# GPSDOCXO_STMv2.net
KiCad netlist of a schematic drawn in EAGLE
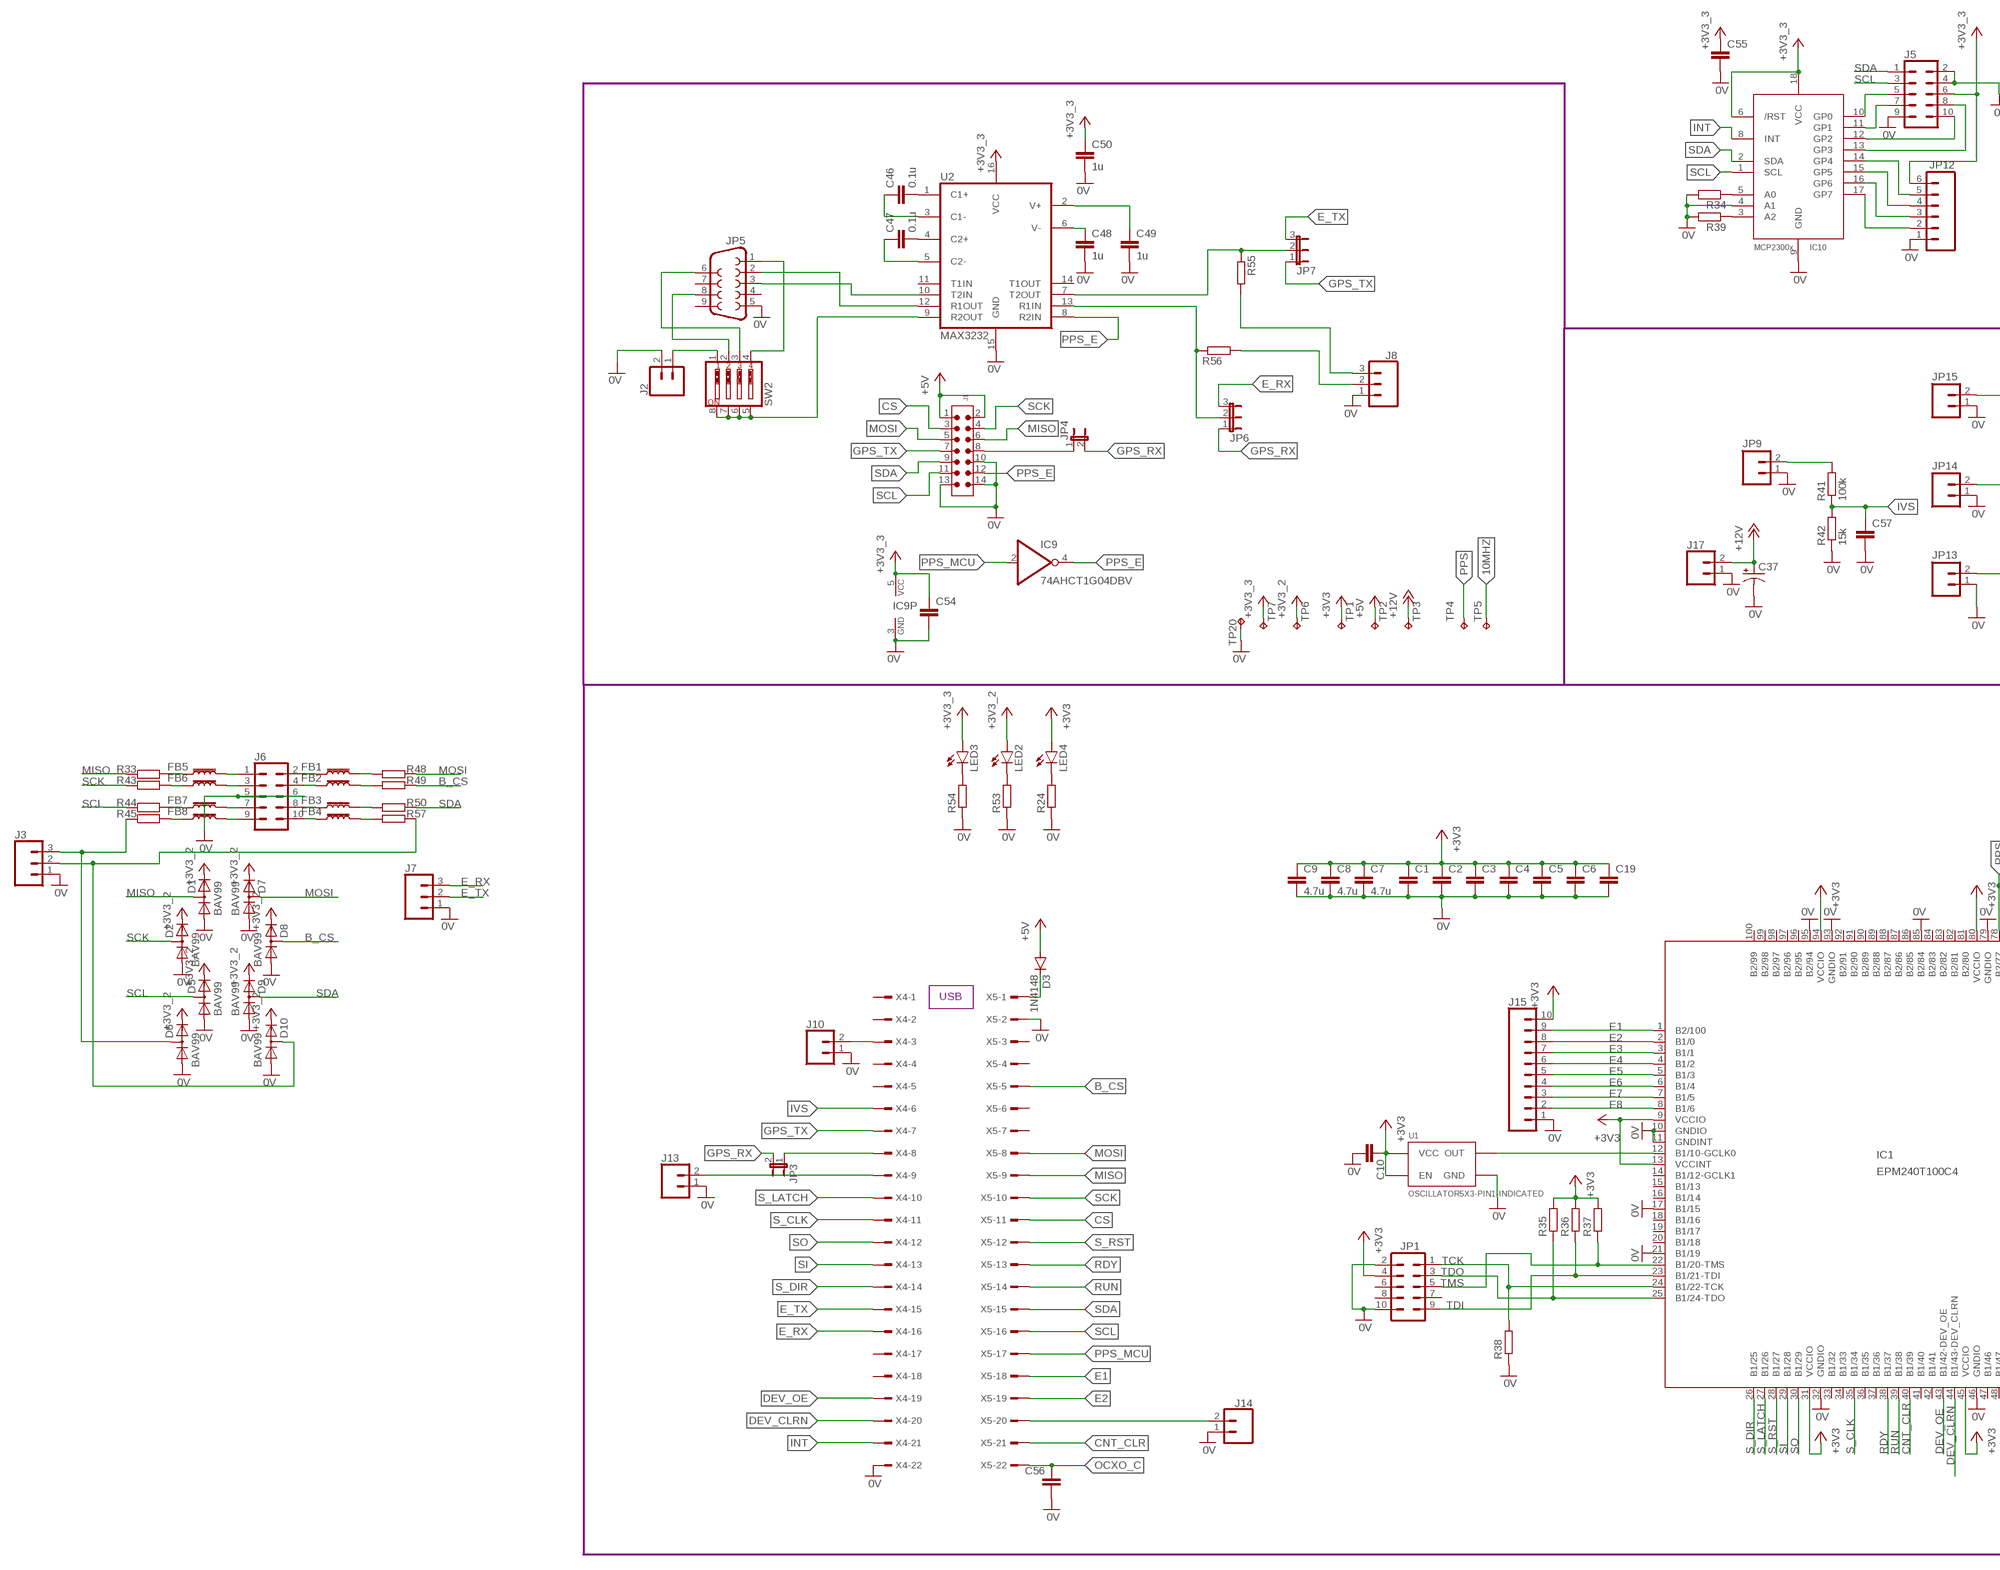
[diagram p0: schematic, sheet 1, part 1 of 2]
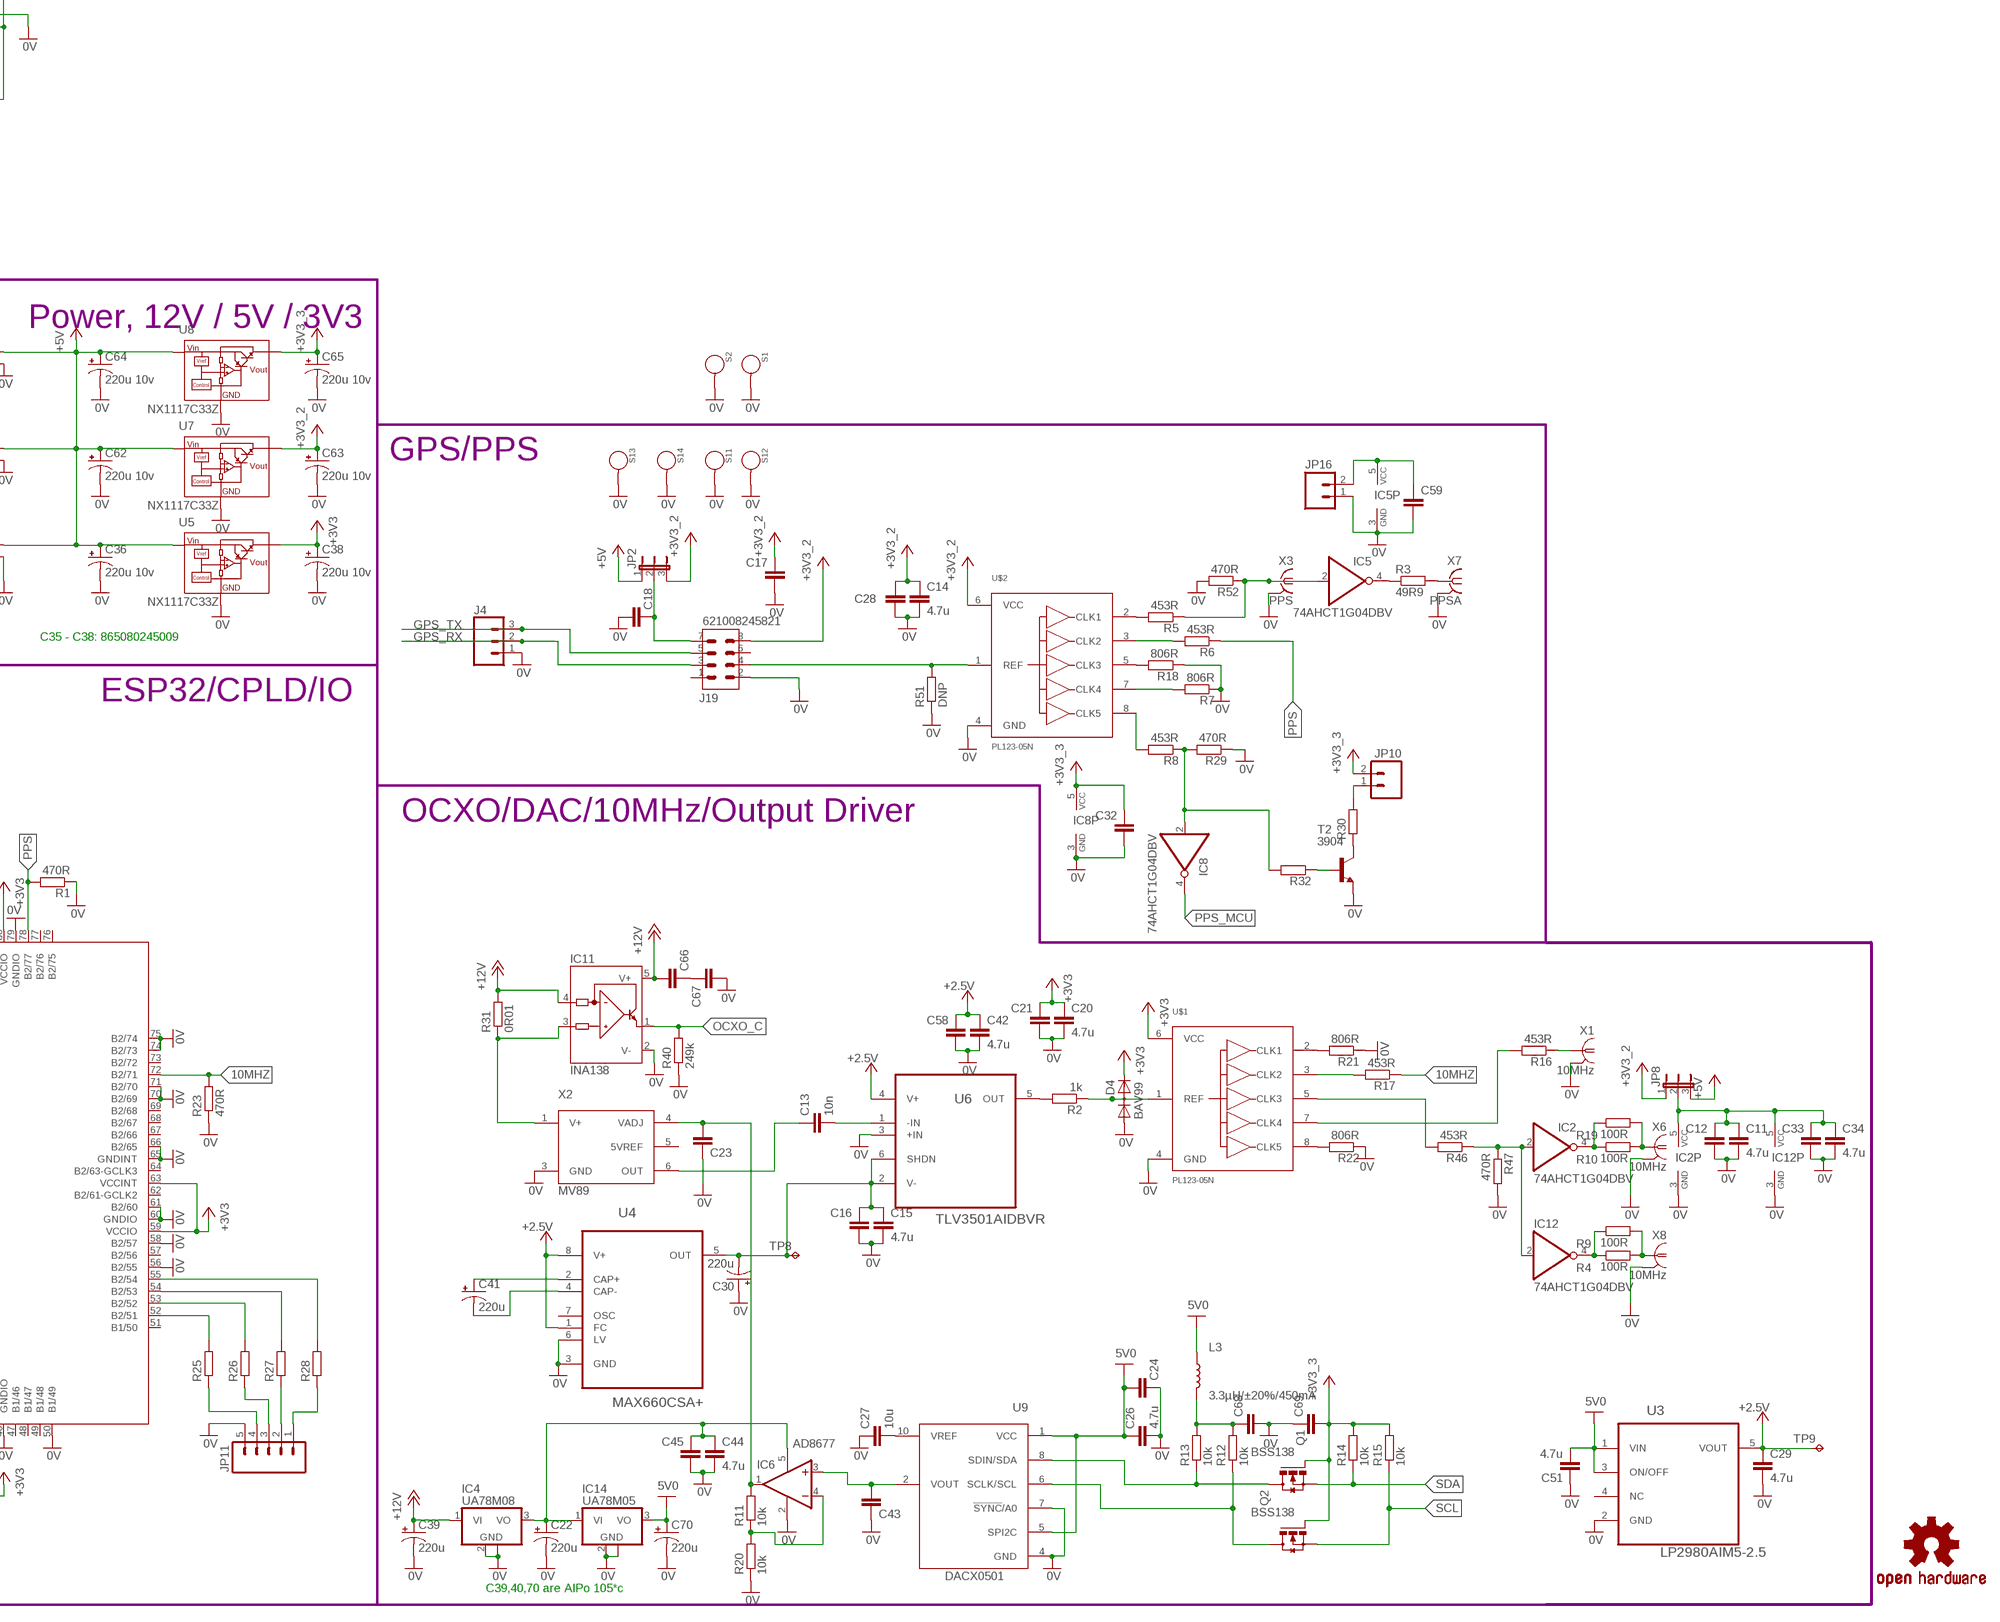
[diagram p1: schematic, sheet 1, part 2 of 2]

(export (version "E")
  (design (tool "Eeschema 10.0.6"))
  (components
    (comp (ref "C1")
      (value "C-EUC0603")
      (footprint "eagle-import:C0603")
      (libsource (lib "eagle-import") (part "C-EUC0603"))
    )
    (comp (ref "C2")
      (value "C-EUC0603")
      (footprint "eagle-import:C0603")
      (libsource (lib "eagle-import") (part "C-EUC0603"))
    )
    (comp (ref "C3")
      (value "C-EUC0603")
      (footprint "eagle-import:C0603")
      (libsource (lib "eagle-import") (part "C-EUC0603"))
    )
    (comp (ref "C4")
      (value "C-EUC0603")
      (footprint "eagle-import:C0603")
      (libsource (lib "eagle-import") (part "C-EUC0603"))
    )
    (comp (ref "C5")
      (value "C-EUC0603")
      (footprint "eagle-import:C0603")
      (libsource (lib "eagle-import") (part "C-EUC0603"))
    )
    (comp (ref "C6")
      (value "C-EUC0603")
      (footprint "eagle-import:C0603")
      (libsource (lib "eagle-import") (part "C-EUC0603"))
    )
    (comp (ref "C7")
      (value "4.7u")
      (footprint "eagle-import:C0805")
      (libsource (lib "eagle-import") (part "C-EUC0805"))
    )
    (comp (ref "C8")
      (value "4.7u")
      (footprint "eagle-import:C0805")
      (libsource (lib "eagle-import") (part "C-EUC0805"))
    )
    (comp (ref "C9")
      (value "4.7u")
      (footprint "eagle-import:C0805")
      (libsource (lib "eagle-import") (part "C-EUC0805"))
    )
    (comp (ref "C10")
      (value "C-EUC0603")
      (footprint "eagle-import:C0603")
      (libsource (lib "eagle-import") (part "C-EUC0603"))
    )
    (comp (ref "C11")
      (value "4.7u")
      (footprint "eagle-import:C0805")
      (libsource (lib "eagle-import") (part "C-EUC0805"))
    )
    (comp (ref "C12")
      (value "C-EUC0603")
      (footprint "eagle-import:C0603")
      (libsource (lib "eagle-import") (part "C-EUC0603"))
    )
    (comp (ref "C13")
      (value "10n")
      (footprint "eagle-import:C0805")
      (libsource (lib "eagle-import") (part "C-EUC0805"))
    )
    (comp (ref "C14")
      (value "4.7u")
      (footprint "eagle-import:C0805")
      (libsource (lib "eagle-import") (part "C-EUC0805"))
    )
    (comp (ref "C15")
      (value "4.7u")
      (footprint "eagle-import:C0805")
      (libsource (lib "eagle-import") (part "C-EUC0805"))
    )
    (comp (ref "C16")
      (value "C-EUC0603")
      (footprint "eagle-import:C0603")
      (libsource (lib "eagle-import") (part "C-EUC0603"))
    )
    (comp (ref "C17")
      (value "C-EUC0805")
      (footprint "eagle-import:C0805")
      (libsource (lib "eagle-import") (part "C-EUC0805"))
    )
    (comp (ref "C18")
      (value "C-EUC0805")
      (footprint "eagle-import:C0805")
      (libsource (lib "eagle-import") (part "C-EUC0805"))
    )
    (comp (ref "C19")
      (value "C-EUC0603")
      (footprint "eagle-import:C0603")
      (libsource (lib "eagle-import") (part "C-EUC0603"))
    )
    (comp (ref "C20")
      (value "4.7u")
      (footprint "eagle-import:C0805")
      (libsource (lib "eagle-import") (part "C-EUC0805"))
    )
    (comp (ref "C21")
      (value "C-EUC0603")
      (footprint "eagle-import:C0603")
      (libsource (lib "eagle-import") (part "C-EUC0603"))
    )
    (comp (ref "C22")
      (value "220u")
      (footprint "eagle-import:153CLV-0605")
      (libsource (lib "eagle-import") (part "CPOL-US153CLV-0605"))
    )
    (comp (ref "C23")
      (value "C-EUC0603")
      (footprint "eagle-import:C0603")
      (libsource (lib "eagle-import") (part "C-EUC0603"))
    )
    (comp (ref "C24")
      (value "C-EUC0603")
      (footprint "eagle-import:C0603")
      (libsource (lib "eagle-import") (part "C-EUC0603"))
    )
    (comp (ref "C26")
      (value "4.7u")
      (footprint "eagle-import:C0805")
      (libsource (lib "eagle-import") (part "C-EUC0805"))
    )
    (comp (ref "C27")
      (value "10u")
      (footprint "eagle-import:C0805")
      (libsource (lib "eagle-import") (part "C-EUC0805"))
    )
    (comp (ref "C28")
      (value "C-EUC0603")
      (footprint "eagle-import:C0603")
      (libsource (lib "eagle-import") (part "C-EUC0603"))
    )
    (comp (ref "C29")
      (value "4.7u")
      (footprint "eagle-import:C0805")
      (libsource (lib "eagle-import") (part "C-EUC0805"))
    )
    (comp (ref "C30")
      (value "220u")
      (footprint "eagle-import:153CLV-1010")
      (libsource (lib "eagle-import") (part "CPOL-US153CLV-1010"))
    )
    (comp (ref "C32")
      (value "C-EUC0603")
      (footprint "eagle-import:C0603")
      (libsource (lib "eagle-import") (part "C-EUC0603"))
    )
    (comp (ref "C33")
      (value "C-EUC0603")
      (footprint "eagle-import:C0603")
      (libsource (lib "eagle-import") (part "C-EUC0603"))
    )
    (comp (ref "C34")
      (value "4.7u")
      (footprint "eagle-import:C0805")
      (libsource (lib "eagle-import") (part "C-EUC0805"))
    )
    (comp (ref "C36")
      (value "220u 10v")
      (footprint "eagle-import:153CLV-0605")
      (libsource (lib "eagle-import") (part "CPOL-US153CLV-0605"))
    )
    (comp (ref "C37")
      (value "CPOL-USE3.5-8")
      (footprint "eagle-import:E3,5-8")
      (libsource (lib "eagle-import") (part "CPOL-USE3.5-8"))
    )
    (comp (ref "C38")
      (value "220u 10v")
      (footprint "eagle-import:153CLV-0605")
      (libsource (lib "eagle-import") (part "CPOL-US153CLV-0605"))
    )
    (comp (ref "C39")
      (value "220u")
      (footprint "eagle-import:153CLV-1010")
      (libsource (lib "eagle-import") (part "CPOL-US153CLV-1010"))
    )
    (comp (ref "C41")
      (value "220u")
      (footprint "eagle-import:153CLV-1010")
      (libsource (lib "eagle-import") (part "CPOL-US153CLV-1010"))
    )
    (comp (ref "C42")
      (value "4.7u")
      (footprint "eagle-import:C0805")
      (libsource (lib "eagle-import") (part "C-EUC0805"))
    )
    (comp (ref "C43")
      (value "C-EUC0603")
      (footprint "eagle-import:C0603")
      (libsource (lib "eagle-import") (part "C-EUC0603"))
    )
    (comp (ref "C44")
      (value "4.7u")
      (footprint "eagle-import:C0805")
      (libsource (lib "eagle-import") (part "C-EUC0805"))
    )
    (comp (ref "C45")
      (value "C-EUC0603")
      (footprint "eagle-import:C0603")
      (libsource (lib "eagle-import") (part "C-EUC0603"))
    )
    (comp (ref "C46")
      (value "0.1u")
      (footprint "eagle-import:C0603")
      (libsource (lib "eagle-import") (part "C-EUC0603"))
    )
    (comp (ref "C47")
      (value "0.1u")
      (footprint "eagle-import:C0603")
      (libsource (lib "eagle-import") (part "C-EUC0603"))
    )
    (comp (ref "C48")
      (value "1u")
      (footprint "eagle-import:C0603")
      (libsource (lib "eagle-import") (part "C-EUC0603"))
    )
    (comp (ref "C49")
      (value "1u")
      (footprint "eagle-import:C0603")
      (libsource (lib "eagle-import") (part "C-EUC0603"))
    )
    (comp (ref "C50")
      (value "1u")
      (footprint "eagle-import:C0603")
      (libsource (lib "eagle-import") (part "C-EUC0603"))
    )
    (comp (ref "C51")
      (value "4.7u")
      (footprint "eagle-import:C0805")
      (libsource (lib "eagle-import") (part "C-EUC0805"))
    )
    (comp (ref "C54")
      (value "C-EUC0603")
      (footprint "eagle-import:C0603")
      (libsource (lib "eagle-import") (part "C-EUC0603"))
    )
    (comp (ref "C55")
      (value "C-EUC0603")
      (footprint "eagle-import:C0603")
      (libsource (lib "eagle-import") (part "C-EUC0603"))
    )
    (comp (ref "C56")
      (value "C-EUC0603")
      (footprint "eagle-import:C0603")
      (libsource (lib "eagle-import") (part "C-EUC0603"))
    )
    (comp (ref "C57")
      (value "C-EUC0603")
      (footprint "eagle-import:C0603")
      (libsource (lib "eagle-import") (part "C-EUC0603"))
    )
    (comp (ref "C58")
      (value "C-EUC0603")
      (footprint "eagle-import:C0603")
      (libsource (lib "eagle-import") (part "C-EUC0603"))
    )
    (comp (ref "C59")
      (value "C-EUC0603")
      (footprint "eagle-import:C0603")
      (libsource (lib "eagle-import") (part "C-EUC0603"))
    )
    (comp (ref "C62")
      (value "220u 10v")
      (footprint "eagle-import:153CLV-0605")
      (libsource (lib "eagle-import") (part "CPOL-US153CLV-0605"))
    )
    (comp (ref "C63")
      (value "220u 10v")
      (footprint "eagle-import:153CLV-0605")
      (libsource (lib "eagle-import") (part "CPOL-US153CLV-0605"))
    )
    (comp (ref "C64")
      (value "220u 10v")
      (footprint "eagle-import:153CLV-0605")
      (libsource (lib "eagle-import") (part "CPOL-US153CLV-0605"))
    )
    (comp (ref "C65")
      (value "220u 10v")
      (footprint "eagle-import:153CLV-0605")
      (libsource (lib "eagle-import") (part "CPOL-US153CLV-0605"))
    )
    (comp (ref "C66")
      (value "C-EUC0603")
      (footprint "eagle-import:C0603")
      (libsource (lib "eagle-import") (part "C-EUC0603"))
    )
    (comp (ref "C67")
      (value "C-EUC0603")
      (footprint "eagle-import:C0603")
      (libsource (lib "eagle-import") (part "C-EUC0603"))
    )
    (comp (ref "C68")
      (value "C-EUC0603")
      (footprint "eagle-import:C0603")
      (libsource (lib "eagle-import") (part "C-EUC0603"))
    )
    (comp (ref "C69")
      (value "C-EUC0603")
      (footprint "eagle-import:C0603")
      (libsource (lib "eagle-import") (part "C-EUC0603"))
    )
    (comp (ref "C70")
      (value "220u")
      (footprint "eagle-import:153CLV-0605")
      (libsource (lib "eagle-import") (part "CPOL-US153CLV-0605"))
    )
    (comp (ref "D1")
      (value "BAV99")
      (footprint "eagle-import:SOT23")
      (libsource (lib "eagle-import") (part "BAV99"))
    )
    (comp (ref "D2")
      (value "BAV99")
      (footprint "eagle-import:SOT23")
      (libsource (lib "eagle-import") (part "BAV99"))
    )
    (comp (ref "D3")
      (value "1N4148")
      (footprint "eagle-import:DO35-7")
      (libsource (lib "eagle-import") (part "1N4148DO35-7"))
    )
    (comp (ref "D4")
      (value "BAV99")
      (footprint "eagle-import:SOT23")
      (libsource (lib "eagle-import") (part "BAV99"))
    )
    (comp (ref "D5")
      (value "BAV99")
      (footprint "eagle-import:SOT23")
      (libsource (lib "eagle-import") (part "BAV99"))
    )
    (comp (ref "D6")
      (value "BAV99")
      (footprint "eagle-import:SOT23")
      (libsource (lib "eagle-import") (part "BAV99"))
    )
    (comp (ref "D7")
      (value "BAV99")
      (footprint "eagle-import:SOT23")
      (libsource (lib "eagle-import") (part "BAV99"))
    )
    (comp (ref "D8")
      (value "BAV99")
      (footprint "eagle-import:SOT23")
      (libsource (lib "eagle-import") (part "BAV99"))
    )
    (comp (ref "D9")
      (value "BAV99")
      (footprint "eagle-import:SOT23")
      (libsource (lib "eagle-import") (part "BAV99"))
    )
    (comp (ref "D10")
      (value "BAV99")
      (footprint "eagle-import:SOT23")
      (libsource (lib "eagle-import") (part "BAV99"))
    )
    (comp (ref "FB1")
      (value "FERRITE_BEAD-0603")
      (footprint "eagle-import:0603")
      (libsource (lib "eagle-import") (part "FERRITE_BEAD-0603"))
    )
    (comp (ref "FB2")
      (value "FERRITE_BEAD-0603")
      (footprint "eagle-import:0603")
      (libsource (lib "eagle-import") (part "FERRITE_BEAD-0603"))
    )
    (comp (ref "FB3")
      (value "FERRITE_BEAD-0603")
      (footprint "eagle-import:0603")
      (libsource (lib "eagle-import") (part "FERRITE_BEAD-0603"))
    )
    (comp (ref "FB4")
      (value "FERRITE_BEAD-0603")
      (footprint "eagle-import:0603")
      (libsource (lib "eagle-import") (part "FERRITE_BEAD-0603"))
    )
    (comp (ref "FB5")
      (value "FERRITE_BEAD-0603")
      (footprint "eagle-import:0603")
      (libsource (lib "eagle-import") (part "FERRITE_BEAD-0603"))
    )
    (comp (ref "FB6")
      (value "FERRITE_BEAD-0603")
      (footprint "eagle-import:0603")
      (libsource (lib "eagle-import") (part "FERRITE_BEAD-0603"))
    )
    (comp (ref "FB7")
      (value "FERRITE_BEAD-0603")
      (footprint "eagle-import:0603")
      (libsource (lib "eagle-import") (part "FERRITE_BEAD-0603"))
    )
    (comp (ref "FB8")
      (value "FERRITE_BEAD-0603")
      (footprint "eagle-import:0603")
      (libsource (lib "eagle-import") (part "FERRITE_BEAD-0603"))
    )
    (comp (ref "IC1")
      (value "EPM240T100C4")
      (footprint "eagle-import:TQFP100")
      (libsource (lib "eagle-import") (part "EPM240T100C4"))
    )
    (comp (ref "IC2")
      (value "74AHCT1G04DBV")
      (footprint "eagle-import:SOT23-5")
      (libsource (lib "eagle-import") (part "741G04DBVAHCT"))
    )
    (comp (ref "IC4")
      (value "UA78M08")
      (footprint "eagle-import:SOT223")
      (libsource (lib "eagle-import") (part "UA78MDCY05"))
    )
    (comp (ref "IC5")
      (value "74AHCT1G04DBV")
      (footprint "eagle-import:SOT23-5")
      (libsource (lib "eagle-import") (part "741G04DBVAHCT"))
    )
    (comp (ref "IC6")
      (value "AD8677")
      (footprint "eagle-import:SOT23-5")
      (libsource (lib "eagle-import") (part "MCP601OT"))
    )
    (comp (ref "IC8")
      (value "74AHCT1G04DBV")
      (footprint "eagle-import:SOT23-5")
      (libsource (lib "eagle-import") (part "741G04DBVAHCT"))
    )
    (comp (ref "IC9")
      (value "74AHCT1G04DBV")
      (footprint "eagle-import:SOT23-5")
      (libsource (lib "eagle-import") (part "741G04DBVAHCT"))
    )
    (comp (ref "IC10")
      (value "MCP23008/SO")
      (footprint "eagle-import:SO18W")
      (libsource (lib "eagle-import") (part "MCP23008/SO"))
    )
    (comp (ref "IC11")
      (value "INA138")
      (footprint "eagle-import:SOT23-5")
      (fields (field (name "MF") "TEXAS INSTRUMENTS") (field (name "MPN") "INA138NA/250"))
      (libsource (lib "eagle-import") (part "INA138"))
    )
    (comp (ref "IC12")
      (value "74AHCT1G04DBV")
      (footprint "eagle-import:SOT23-5")
      (libsource (lib "eagle-import") (part "741G04DBVAHCT"))
    )
    (comp (ref "IC14")
      (value "UA78M05")
      (footprint "eagle-import:SOT223")
      (libsource (lib "eagle-import") (part "UA78MDCY05"))
    )
    (comp (ref "J1")
      (value "6120XX21621_61201421621")
      (footprint "eagle-import:61201421621")
      (libsource (lib "eagle-import") (part "6120XX21621_61201421621"))
    )
    (comp (ref "J2")
      (value "CONN_02")
      (footprint "eagle-import:1X02")
      (libsource (lib "eagle-import") (part "CONN_02"))
    )
    (comp (ref "J3")
      (value "M03POLAR")
      (footprint "eagle-import:MOLEX-1X3")
      (libsource (lib "eagle-import") (part "M03POLAR"))
    )
    (comp (ref "J4")
      (value "CONN_03")
      (footprint "eagle-import:1X03")
      (libsource (lib "eagle-import") (part "CONN_03"))
    )
    (comp (ref "J5")
      (value "CONN_05X2SHD-NS")
      (footprint "eagle-import:2X5-SHROUDED-NS")
      (libsource (lib "eagle-import") (part "CONN_05X2SHD-NS"))
    )
    (comp (ref "J6")
      (value "CONN_05X2RAF")
      (footprint "eagle-import:2X5-RAF")
      (libsource (lib "eagle-import") (part "CONN_05X2RAF"))
    )
    (comp (ref "J7")
      (value "M03POLAR")
      (footprint "eagle-import:MOLEX-1X3")
      (libsource (lib "eagle-import") (part "M03POLAR"))
    )
    (comp (ref "J8")
      (value "M03POLAR")
      (footprint "eagle-import:MOLEX-1X3")
      (libsource (lib "eagle-import") (part "M03POLAR"))
    )
    (comp (ref "J10")
      (value "CONN_02")
      (footprint "eagle-import:1X02")
      (libsource (lib "eagle-import") (part "CONN_02"))
    )
    (comp (ref "J13")
      (value "CONN_02")
      (footprint "eagle-import:1X02")
      (libsource (lib "eagle-import") (part "CONN_02"))
    )
    (comp (ref "J14")
      (value "CONN_02")
      (footprint "eagle-import:1X02")
      (libsource (lib "eagle-import") (part "CONN_02"))
    )
    (comp (ref "J15")
      (value "CONN_10NO_SILK_PTH_FEMALE")
      (footprint "eagle-import:1X10_NO_SILK")
      (libsource (lib "eagle-import") (part "CONN_10NO_SILK_PTH_FEMALE"))
    )
    (comp (ref "J17")
      (value "CONN_025MM")
      (footprint "eagle-import:SCREWTERMINAL-5MM-2")
      (libsource (lib "eagle-import") (part "CONN_025MM"))
    )
    (comp (ref "J19")
      (value "621008245821")
      (footprint "eagle-import:621008245821")
      (fields
        (field (name "MANUFACTURER") "Wurth Elektronik")
        (field (name "MPN") "621008245821 ")
        (field (name "CREATED_BY") "PCBLayout.com")
      )
      (libsource (lib "eagle-import") (part "621008245821"))
    )
    (comp (ref "JP1")
      (value "M05X2SHD-NS")
      (footprint "eagle-import:2X5-SHROUDED-NS")
      (libsource (lib "eagle-import") (part "M05X2SHD-NS"))
    )
    (comp (ref "JP2")
      (value "JP2E")
      (footprint "eagle-import:JP2")
      (libsource (lib "eagle-import") (part "JP2E"))
    )
    (comp (ref "JP3")
      (value "JP1E")
      (footprint "eagle-import:JP1")
      (libsource (lib "eagle-import") (part "JP1E"))
    )
    (comp (ref "JP4")
      (value "JP1E")
      (footprint "eagle-import:JP1")
      (libsource (lib "eagle-import") (part "JP1E"))
    )
    (comp (ref "JP5")
      (value "DB9FEMALE")
      (footprint "eagle-import:DB9")
      (libsource (lib "eagle-import") (part "DB9FEMALE"))
    )
    (comp (ref "JP6")
      (value "JP2E")
      (footprint "eagle-import:JP2")
      (libsource (lib "eagle-import") (part "JP2E"))
    )
    (comp (ref "JP7")
      (value "JP2E")
      (footprint "eagle-import:JP2")
      (libsource (lib "eagle-import") (part "JP2E"))
    )
    (comp (ref "JP8")
      (value "JP2E")
      (footprint "eagle-import:JP2")
      (libsource (lib "eagle-import") (part "JP2E"))
    )
    (comp (ref "JP9")
      (value "M02POLAR")
      (footprint "eagle-import:MOLEX-1X2")
      (libsource (lib "eagle-import") (part "M02POLAR"))
    )
    (comp (ref "JP10")
      (value "M02POLAR")
      (footprint "eagle-import:MOLEX-1X2")
      (libsource (lib "eagle-import") (part "M02POLAR"))
    )
    (comp (ref "JP11")
      (value "M05NO_SILK")
      (footprint "eagle-import:1X05_NO_SILK")
      (libsource (lib "eagle-import") (part "M05NO_SILK"))
    )
    (comp (ref "JP12")
      (value "M06SILK_FEMALE_PTH")
      (footprint "eagle-import:1X06")
      (libsource (lib "eagle-import") (part "M06SILK_FEMALE_PTH"))
    )
    (comp (ref "JP13")
      (value "M02POLAR")
      (footprint "eagle-import:MOLEX-1X2")
      (libsource (lib "eagle-import") (part "M02POLAR"))
    )
    (comp (ref "JP14")
      (value "M02POLAR")
      (footprint "eagle-import:MOLEX-1X2")
      (libsource (lib "eagle-import") (part "M02POLAR"))
    )
    (comp (ref "JP15")
      (value "M02POLAR")
      (footprint "eagle-import:MOLEX-1X2")
      (libsource (lib "eagle-import") (part "M02POLAR"))
    )
    (comp (ref "JP16")
      (value "M02POLAR")
      (footprint "eagle-import:MOLEX-1X2")
      (libsource (lib "eagle-import") (part "M02POLAR"))
    )
    (comp (ref "L3")
      (value "3.3µH/±20%/450mA")
      (footprint "eagle-import:0805")
      (libsource (lib "eagle-import") (part "INDUCTOR-0805-3.3UH"))
    )
    (comp (ref "LED2")
      (value "LED5MM")
      (footprint "eagle-import:LED5MM")
      (libsource (lib "eagle-import") (part "LED5MM"))
    )
    (comp (ref "LED3")
      (value "LED5MM")
      (footprint "eagle-import:LED5MM")
      (libsource (lib "eagle-import") (part "LED5MM"))
    )
    (comp (ref "LED4")
      (value "LED5MM")
      (footprint "eagle-import:LED5MM")
      (libsource (lib "eagle-import") (part "LED5MM"))
    )
    (comp (ref "LOGO1")
      (value "OSHW-LOGOL")
      (footprint "eagle-import:OSHW-LOGO-L")
      (libsource (lib "eagle-import") (part "OSHW-LOGOL"))
    )
    (comp (ref "Q1")
      (value "BSS138")
      (footprint "eagle-import:SOT23-3")
      (fields
        (field (name "DIGIKEY_PART_NUMBER") "BSS138CT-ND")
        (field (name "MANUFACTURER") "ON Semiconductor")
        (field (name "CREATED_BY") "PCBLayout.com")
      )
      (libsource (lib "eagle-import") (part "BSS138"))
    )
    (comp (ref "Q2")
      (value "BSS138")
      (footprint "eagle-import:SOT23-3")
      (fields
        (field (name "DIGIKEY_PART_NUMBER") "BSS138CT-ND")
        (field (name "MANUFACTURER") "ON Semiconductor")
        (field (name "CREATED_BY") "PCBLayout.com")
      )
      (libsource (lib "eagle-import") (part "BSS138"))
    )
    (comp (ref "R1")
      (value "470R")
      (footprint "eagle-import:R0603")
      (libsource (lib "eagle-import") (part "R-EU_R0603"))
    )
    (comp (ref "R2")
      (value "1k")
      (footprint "eagle-import:R0603")
      (libsource (lib "eagle-import") (part "R-EU_R0603"))
    )
    (comp (ref "R3")
      (value "49R9")
      (footprint "eagle-import:R0805")
      (libsource (lib "eagle-import") (part "R-EU_R0805"))
    )
    (comp (ref "R4")
      (value "100R")
      (footprint "eagle-import:R0805")
      (libsource (lib "eagle-import") (part "R-EU_R0805"))
    )
    (comp (ref "R5")
      (value "453R")
      (footprint "eagle-import:R0603")
      (libsource (lib "eagle-import") (part "R-EU_R0603"))
    )
    (comp (ref "R6")
      (value "453R")
      (footprint "eagle-import:R0603")
      (libsource (lib "eagle-import") (part "R-EU_R0603"))
    )
    (comp (ref "R7")
      (value "806R")
      (footprint "eagle-import:R0603")
      (libsource (lib "eagle-import") (part "R-EU_R0603"))
    )
    (comp (ref "R8")
      (value "453R")
      (footprint "eagle-import:R0603")
      (libsource (lib "eagle-import") (part "R-EU_R0603"))
    )
    (comp (ref "R9")
      (value "100R")
      (footprint "eagle-import:R0805")
      (libsource (lib "eagle-import") (part "R-EU_R0805"))
    )
    (comp (ref "R10")
      (value "100R")
      (footprint "eagle-import:R0805")
      (libsource (lib "eagle-import") (part "R-EU_R0805"))
    )
    (comp (ref "R11")
      (value "10k")
      (footprint "eagle-import:R0603")
      (libsource (lib "eagle-import") (part "R-EU_R0603"))
    )
    (comp (ref "R12")
      (value "10k")
      (footprint "eagle-import:R0603")
      (libsource (lib "eagle-import") (part "R-EU_R0603"))
    )
    (comp (ref "R13")
      (value "10k")
      (footprint "eagle-import:R0603")
      (libsource (lib "eagle-import") (part "R-EU_R0603"))
    )
    (comp (ref "R14")
      (value "10k")
      (footprint "eagle-import:R0603")
      (libsource (lib "eagle-import") (part "R-EU_R0603"))
    )
    (comp (ref "R15")
      (value "10k")
      (footprint "eagle-import:R0603")
      (libsource (lib "eagle-import") (part "R-EU_R0603"))
    )
    (comp (ref "R16")
      (value "453R")
      (footprint "eagle-import:R0603")
      (libsource (lib "eagle-import") (part "R-EU_R0603"))
    )
    (comp (ref "R17")
      (value "453R")
      (footprint "eagle-import:R0603")
      (libsource (lib "eagle-import") (part "R-EU_R0603"))
    )
    (comp (ref "R18")
      (value "806R")
      (footprint "eagle-import:R0603")
      (libsource (lib "eagle-import") (part "R-EU_R0603"))
    )
    (comp (ref "R19")
      (value "100R")
      (footprint "eagle-import:R0805")
      (libsource (lib "eagle-import") (part "R-EU_R0805"))
    )
    (comp (ref "R20")
      (value "10k")
      (footprint "eagle-import:R0603")
      (libsource (lib "eagle-import") (part "R-EU_R0603"))
    )
    (comp (ref "R21")
      (value "806R")
      (footprint "eagle-import:R0603")
      (libsource (lib "eagle-import") (part "R-EU_R0603"))
    )
    (comp (ref "R22")
      (value "806R")
      (footprint "eagle-import:R0603")
      (libsource (lib "eagle-import") (part "R-EU_R0603"))
    )
    (comp (ref "R23")
      (value "470R")
      (footprint "eagle-import:R0603")
      (libsource (lib "eagle-import") (part "R-EU_R0603"))
    )
    (comp (ref "R24")
      (value "R-EU_R0603")
      (footprint "eagle-import:R0603")
      (libsource (lib "eagle-import") (part "R-EU_R0603"))
    )
    (comp (ref "R25")
      (value "R-EU_R0603")
      (footprint "eagle-import:R0603")
      (libsource (lib "eagle-import") (part "R-EU_R0603"))
    )
    (comp (ref "R26")
      (value "R-EU_R0603")
      (footprint "eagle-import:R0603")
      (libsource (lib "eagle-import") (part "R-EU_R0603"))
    )
    (comp (ref "R27")
      (value "R-EU_R0603")
      (footprint "eagle-import:R0603")
      (libsource (lib "eagle-import") (part "R-EU_R0603"))
    )
    (comp (ref "R28")
      (value "R-EU_R0603")
      (footprint "eagle-import:R0603")
      (libsource (lib "eagle-import") (part "R-EU_R0603"))
    )
    (comp (ref "R29")
      (value "470R")
      (footprint "eagle-import:R0603")
      (libsource (lib "eagle-import") (part "R-EU_R0603"))
    )
    (comp (ref "R30")
      (value "R-EU_R0603")
      (footprint "eagle-import:R0603")
      (libsource (lib "eagle-import") (part "R-EU_R0603"))
    )
    (comp (ref "R31")
      (value "0R01")
      (footprint "eagle-import:R1210")
      (libsource (lib "eagle-import") (part "R-EU_R1210"))
    )
    (comp (ref "R32")
      (value "R-EU_R0603")
      (footprint "eagle-import:R0603")
      (libsource (lib "eagle-import") (part "R-EU_R0603"))
    )
    (comp (ref "R33")
      (value "R-EU_R0603")
      (footprint "eagle-import:R0603")
      (libsource (lib "eagle-import") (part "R-EU_R0603"))
    )
    (comp (ref "R34")
      (value "R-EU_R0603")
      (footprint "eagle-import:R0603")
      (libsource (lib "eagle-import") (part "R-EU_R0603"))
    )
    (comp (ref "R35")
      (value "R-EU_R0603")
      (footprint "eagle-import:R0603")
      (libsource (lib "eagle-import") (part "R-EU_R0603"))
    )
    (comp (ref "R36")
      (value "R-EU_R0603")
      (footprint "eagle-import:R0603")
      (libsource (lib "eagle-import") (part "R-EU_R0603"))
    )
    (comp (ref "R37")
      (value "R-EU_R0603")
      (footprint "eagle-import:R0603")
      (libsource (lib "eagle-import") (part "R-EU_R0603"))
    )
    (comp (ref "R38")
      (value "R-EU_R0603")
      (footprint "eagle-import:R0603")
      (libsource (lib "eagle-import") (part "R-EU_R0603"))
    )
    (comp (ref "R39")
      (value "R-EU_R0603")
      (footprint "eagle-import:R0603")
      (libsource (lib "eagle-import") (part "R-EU_R0603"))
    )
    (comp (ref "R40")
      (value "249k")
      (footprint "eagle-import:R0603")
      (libsource (lib "eagle-import") (part "R-EU_R0603"))
    )
    (comp (ref "R41")
      (value "100k")
      (footprint "eagle-import:0204_7")
      (libsource (lib "eagle-import") (part "R-EU_0204/7"))
    )
    (comp (ref "R42")
      (value "15k")
      (footprint "eagle-import:R0603")
      (libsource (lib "eagle-import") (part "R-EU_R0603"))
    )
    (comp (ref "R43")
      (value "R-EU_R0603")
      (footprint "eagle-import:R0603")
      (libsource (lib "eagle-import") (part "R-EU_R0603"))
    )
    (comp (ref "R44")
      (value "R-EU_R0603")
      (footprint "eagle-import:R0603")
      (libsource (lib "eagle-import") (part "R-EU_R0603"))
    )
    (comp (ref "R45")
      (value "R-EU_R0603")
      (footprint "eagle-import:R0603")
      (libsource (lib "eagle-import") (part "R-EU_R0603"))
    )
    (comp (ref "R46")
      (value "453R")
      (footprint "eagle-import:R0603")
      (libsource (lib "eagle-import") (part "R-EU_R0603"))
    )
    (comp (ref "R47")
      (value "470R")
      (footprint "eagle-import:R0603")
      (libsource (lib "eagle-import") (part "R-EU_R0603"))
    )
    (comp (ref "R48")
      (value "R-EU_R0603")
      (footprint "eagle-import:R0603")
      (libsource (lib "eagle-import") (part "R-EU_R0603"))
    )
    (comp (ref "R49")
      (value "R-EU_R0603")
      (footprint "eagle-import:R0603")
      (libsource (lib "eagle-import") (part "R-EU_R0603"))
    )
    (comp (ref "R50")
      (value "R-EU_R0603")
      (footprint "eagle-import:R0603")
      (libsource (lib "eagle-import") (part "R-EU_R0603"))
    )
    (comp (ref "R51")
      (value "DNP")
      (footprint "eagle-import:R0603")
      (libsource (lib "eagle-import") (part "R-EU_R0603"))
    )
    (comp (ref "R52")
      (value "470R")
      (footprint "eagle-import:R0603")
      (libsource (lib "eagle-import") (part "R-EU_R0603"))
    )
    (comp (ref "R53")
      (value "R-EU_R0603")
      (footprint "eagle-import:R0603")
      (libsource (lib "eagle-import") (part "R-EU_R0603"))
    )
    (comp (ref "R54")
      (value "R-EU_R0603")
      (footprint "eagle-import:R0603")
      (libsource (lib "eagle-import") (part "R-EU_R0603"))
    )
    (comp (ref "R55")
      (value "R-EU_R0603")
      (footprint "eagle-import:R0603")
      (libsource (lib "eagle-import") (part "R-EU_R0603"))
    )
    (comp (ref "R56")
      (value "R-EU_R0603")
      (footprint "eagle-import:R0603")
      (libsource (lib "eagle-import") (part "R-EU_R0603"))
    )
    (comp (ref "R57")
      (value "R-EU_R0603")
      (footprint "eagle-import:R0603")
      (libsource (lib "eagle-import") (part "R-EU_R0603"))
    )
    (comp (ref "S1")
      (value "STANDOFF_ELECTRICAL")
      (footprint "eagle-import:STANDOFF-ELECTRICAL")
      (libsource (lib "eagle-import") (part "STANDOFF_ELECTRICAL"))
    )
    (comp (ref "S2")
      (value "STANDOFF_ELECTRICAL")
      (footprint "eagle-import:STANDOFF-ELECTRICAL")
      (libsource (lib "eagle-import") (part "STANDOFF_ELECTRICAL"))
    )
    (comp (ref "S11")
      (value "STANDOFF_ELECTRICAL")
      (footprint "eagle-import:STANDOFF-ELECTRICAL")
      (libsource (lib "eagle-import") (part "STANDOFF_ELECTRICAL"))
    )
    (comp (ref "S12")
      (value "STANDOFF_ELECTRICAL")
      (footprint "eagle-import:STANDOFF-ELECTRICAL")
      (libsource (lib "eagle-import") (part "STANDOFF_ELECTRICAL"))
    )
    (comp (ref "S13")
      (value "STANDOFF_ELECTRICAL")
      (footprint "eagle-import:STANDOFF-ELECTRICAL")
      (libsource (lib "eagle-import") (part "STANDOFF_ELECTRICAL"))
    )
    (comp (ref "S14")
      (value "STANDOFF_ELECTRICAL")
      (footprint "eagle-import:STANDOFF-ELECTRICAL")
      (libsource (lib "eagle-import") (part "STANDOFF_ELECTRICAL"))
    )
    (comp (ref "SW2")
      (value "SW_DIP-4")
      (footprint "eagle-import:EDG-04")
      (libsource (lib "eagle-import") (part "SW_DIP-4"))
    )
    (comp (ref "T2")
      (value "3904")
      (footprint "eagle-import:SOT23-BEC")
      (libsource (lib "eagle-import") (part "-NPN-SOT23-BECMMBT3904LT1"))
    )
    (comp (ref "TP1")
      (value "TPPAD1-13")
      (footprint "eagle-import:P1-13")
      (libsource (lib "eagle-import") (part "TPPAD1-13"))
    )
    (comp (ref "TP2")
      (value "TPPAD1-13")
      (footprint "eagle-import:P1-13")
      (libsource (lib "eagle-import") (part "TPPAD1-13"))
    )
    (comp (ref "TP3")
      (value "TPPAD1-13")
      (footprint "eagle-import:P1-13")
      (libsource (lib "eagle-import") (part "TPPAD1-13"))
    )
    (comp (ref "TP4")
      (value "TPTP13R")
      (footprint "eagle-import:TP13R")
      (libsource (lib "eagle-import") (part "TPTP13R"))
    )
    (comp (ref "TP5")
      (value "TPTP13R")
      (footprint "eagle-import:TP13R")
      (libsource (lib "eagle-import") (part "TPTP13R"))
    )
    (comp (ref "TP6")
      (value "TPPAD1-13")
      (footprint "eagle-import:P1-13")
      (libsource (lib "eagle-import") (part "TPPAD1-13"))
    )
    (comp (ref "TP7")
      (value "TPPAD1-13")
      (footprint "eagle-import:P1-13")
      (libsource (lib "eagle-import") (part "TPPAD1-13"))
    )
    (comp (ref "TP8")
      (value "TPPAD1-13")
      (footprint "eagle-import:P1-13")
      (libsource (lib "eagle-import") (part "TPPAD1-13"))
    )
    (comp (ref "TP9")
      (value "TPPAD1-13")
      (footprint "eagle-import:P1-13")
      (libsource (lib "eagle-import") (part "TPPAD1-13"))
    )
    (comp (ref "TP20")
      (value "TPPAD1-13")
      (footprint "eagle-import:P1-13")
      (libsource (lib "eagle-import") (part "TPPAD1-13"))
    )
    (comp (ref "U$1")
      (value "PL123-05N")
      (footprint "eagle-import:SOIC-8")
      (libsource (lib "eagle-import") (part "PL123-05N"))
    )
    (comp (ref "U$2")
      (value "PL123-05N")
      (footprint "eagle-import:SOIC-8")
      (libsource (lib "eagle-import") (part "PL123-05N"))
    )
    (comp (ref "U1")
      (value "OSCILLATOR5X3-PIN1-INDICATED")
      (footprint "eagle-import:CRYSTAL-OSC-SMD-5X3")
      (libsource (lib "eagle-import") (part "OSCILLATOR5X3-PIN1-INDICATED"))
    )
    (comp (ref "U2")
      (value "MAX3232")
      (footprint "eagle-import:SO16")
      (libsource (lib "eagle-import") (part "MAX2323SOIC16"))
    )
    (comp (ref "U3")
      (value "LP2980AIM5-2.5")
      (footprint "eagle-import:SOT95P284X119-5N")
      (fields (field (name "MPN") "LP2980AIM5-3.0"))
      (libsource (lib "eagle-import") (part "LP2980AIM5-3.0"))
    )
    (comp (ref "U4")
      (value "MAX660CSA+")
      (footprint "eagle-import:SOIC127P600X175-8N")
      (libsource (lib "eagle-import") (part "MAX660CSA+"))
    )
    (comp (ref "U5")
      (value "NX1117C33Z")
      (footprint "eagle-import:SOT223")
      (fields (field (name "TOLERANCE") "1.25%") (field (name "VOLTAGE") "5.0V"))
      (libsource (lib "eagle-import") (part "NX1117CZ33"))
    )
    (comp (ref "U6")
      (value "TLV3501AIDBVR")
      (footprint "eagle-import:SOT95P280X145-6N")
      (fields (field (name "MPN") "TLV3501AIDBVT"))
      (libsource (lib "eagle-import") (part "TLV3501AIDBVT"))
    )
    (comp (ref "U7")
      (value "NX1117C33Z")
      (footprint "eagle-import:SOT223")
      (fields (field (name "TOLERANCE") "1.25%") (field (name "VOLTAGE") "5.0V"))
      (libsource (lib "eagle-import") (part "NX1117CZ33"))
    )
    (comp (ref "U8")
      (value "NX1117C33Z")
      (footprint "eagle-import:SOT223")
      (fields (field (name "TOLERANCE") "1.25%") (field (name "VOLTAGE") "5.0V"))
      (libsource (lib "eagle-import") (part "NX1117CZ33"))
    )
    (comp (ref "U9")
      (value "DACX0501")
      (footprint "eagle-import:VSSOP-10")
      (libsource (lib "eagle-import") (part "DACX0501"))
    )
    (comp (ref "X1")
      (value "10MHz")
      (footprint "eagle-import:AMP_227161")
      (fields (field (name "MF") "TYCO ELECTRONICS") (field (name "MPN") "1-227161"))
      (libsource (lib "eagle-import") (part "?2271611--0"))
    )
    (comp (ref "X2")
      (value "MV89")
      (footprint "eagle-import:MV89")
      (libsource (lib "eagle-import") (part "MV89"))
    )
    (comp (ref "X3")
      (value "PPS")
      (footprint "eagle-import:BU-SMA-V")
      (libsource (lib "eagle-import") (part "BU-SMA-V"))
    )
    (comp (ref "X4")
      (value "TSW-122-07-G-S")
      (footprint "eagle-import:TSW-122-XX-G-S")
      (fields (field (name "MF") "Samtec Inc."))
      (libsource (lib "eagle-import") (part "TSW-122--G-S07"))
    )
    (comp (ref "X5")
      (value "TSW-122-07-G-S")
      (footprint "eagle-import:TSW-122-XX-G-S")
      (fields (field (name "MF") "Samtec Inc."))
      (libsource (lib "eagle-import") (part "TSW-122--G-S07"))
    )
    (comp (ref "X6")
      (value "10MHz")
      (footprint "eagle-import:AMP_227161")
      (fields (field (name "MF") "TYCO ELECTRONICS") (field (name "MPN") "1-227161"))
      (libsource (lib "eagle-import") (part "?2271611--0"))
    )
    (comp (ref "X7")
      (value "PPSA")
      (footprint "eagle-import:BU-SMA-V")
      (libsource (lib "eagle-import") (part "BU-SMA-V"))
    )
    (comp (ref "X8")
      (value "10MHz")
      (footprint "eagle-import:AMP_227161")
      (fields (field (name "MF") "TYCO ELECTRONICS") (field (name "MPN") "1-227161"))
      (libsource (lib "eagle-import") (part "?2271611--0"))
    )
  )
  (nets
    (net (code "1") (name "+2.5V") (class "Default")
      (node (ref "C29") (pin "1") (pinfunction "1_1") (pintype "passive"))
      (node (ref "C42") (pin "1") (pinfunction "1_1") (pintype "passive"))
      (node (ref "C58") (pin "1") (pinfunction "1_1") (pintype "passive"))
      (node (ref "TP9") (pin "TP") (pinfunction "TP_TP") (pintype "input"))
      (node (ref "U3") (pin "5") (pinfunction "VOUT_5") (pintype "output"))
      (node (ref "U4") (pin "1") (pinfunction "FC_1") (pintype "input"))
      (node (ref "U4") (pin "8") (pinfunction "V+_8") (pintype "power_in"))
      (node (ref "U6") (pin "4") (pinfunction "V+_4") (pintype "power_in"))
    )
    (net (code "2") (name "+3V3") (class "Default")
      (node (ref "C1") (pin "1") (pinfunction "1_1") (pintype "passive"))
      (node (ref "C10") (pin "1") (pinfunction "1_1") (pintype "passive"))
      (node (ref "C19") (pin "1") (pinfunction "1_1") (pintype "passive"))
      (node (ref "C2") (pin "1") (pinfunction "1_1") (pintype "passive"))
      (node (ref "C20") (pin "1") (pinfunction "1_1") (pintype "passive"))
      (node (ref "C21") (pin "1") (pinfunction "1_1") (pintype "passive"))
      (node (ref "C3") (pin "1") (pinfunction "1_1") (pintype "passive"))
      (node (ref "C38") (pin "+") (pinfunction "+_+") (pintype "passive"))
      (node (ref "C4") (pin "1") (pinfunction "1_1") (pintype "passive"))
      (node (ref "C5") (pin "1") (pinfunction "1_1") (pintype "passive"))
      (node (ref "C6") (pin "1") (pinfunction "1_1") (pintype "passive"))
      (node (ref "C7") (pin "1") (pinfunction "1_1") (pintype "passive"))
      (node (ref "C8") (pin "1") (pinfunction "1_1") (pintype "passive"))
      (node (ref "C9") (pin "1") (pinfunction "1_1") (pintype "passive"))
      (node (ref "D4") (pin "2") (pinfunction "K2_2") (pintype "passive"))
      (node (ref "IC1") (pin "13") (pinfunction "VCCINT_13") (pintype "power_in"))
      (node (ref "IC1") (pin "31") (pinfunction "VCCIO_31") (pintype "power_in"))
      (node (ref "IC1") (pin "45") (pinfunction "VCCIO_45") (pintype "power_in"))
      (node (ref "IC1") (pin "59") (pinfunction "VCCIO_59") (pintype "power_in"))
      (node (ref "IC1") (pin "63") (pinfunction "VCCINT_63") (pintype "power_in"))
      (node (ref "IC1") (pin "80") (pinfunction "VCCIO_80") (pintype "power_in"))
      (node (ref "IC1") (pin "9") (pinfunction "VCCIO_9") (pintype "power_in"))
      (node (ref "IC1") (pin "94") (pinfunction "VCCIO_94") (pintype "power_in"))
      (node (ref "J15") (pin "10") (pinfunction "10_10") (pintype "passive"))
      (node (ref "JP1") (pin "4") (pinfunction "4_4") (pintype "passive"))
      (node (ref "LED4") (pin "A") (pinfunction "A_A") (pintype "passive"))
      (node (ref "R35") (pin "2") (pinfunction "2_2") (pintype "passive"))
      (node (ref "R36") (pin "2") (pinfunction "2_2") (pintype "passive"))
      (node (ref "R37") (pin "2") (pinfunction "2_2") (pintype "passive"))
      (node (ref "TP1") (pin "TP") (pinfunction "TP_TP") (pintype "input"))
      (node (ref "U$1") (pin "6") (pinfunction "VCC_6") (pintype "bidirectional"))
      (node (ref "U1") (pin "1") (pinfunction "EN_1") (pintype "bidirectional"))
      (node (ref "U1") (pin "4") (pinfunction "VCC_4") (pintype "bidirectional"))
      (node (ref "U5") (pin "2") (pinfunction "VOUT_2") (pintype "output"))
      (node (ref "U5") (pin "4") (pinfunction "VOUT_4") (pintype "output"))
    )
    (net (code "3") (name "+3V3_2") (class "Default")
      (node (ref "C14") (pin "1") (pinfunction "1_1") (pintype "passive"))
      (node (ref "C17") (pin "1") (pinfunction "1_1") (pintype "passive"))
      (node (ref "C28") (pin "1") (pinfunction "1_1") (pintype "passive"))
      (node (ref "C63") (pin "+") (pinfunction "+_+") (pintype "passive"))
      (node (ref "D1") (pin "2") (pinfunction "K2_2") (pintype "passive"))
      (node (ref "D10") (pin "2") (pinfunction "K2_2") (pintype "passive"))
      (node (ref "D2") (pin "2") (pinfunction "K2_2") (pintype "passive"))
      (node (ref "D5") (pin "2") (pinfunction "K2_2") (pintype "passive"))
      (node (ref "D6") (pin "2") (pinfunction "K2_2") (pintype "passive"))
      (node (ref "D7") (pin "2") (pinfunction "K2_2") (pintype "passive"))
      (node (ref "D8") (pin "2") (pinfunction "K2_2") (pintype "passive"))
      (node (ref "D9") (pin "2") (pinfunction "K2_2") (pintype "passive"))
      (node (ref "J19") (pin "8") (pinfunction "8_8") (pintype "passive"))
      (node (ref "JP2") (pin "3") (pinfunction "3_3") (pintype "passive"))
      (node (ref "JP8") (pin "1") (pinfunction "1_1") (pintype "passive"))
      (node (ref "LED2") (pin "A") (pinfunction "A_A") (pintype "passive"))
      (node (ref "TP6") (pin "TP") (pinfunction "TP_TP") (pintype "input"))
      (node (ref "U$2") (pin "6") (pinfunction "VCC_6") (pintype "bidirectional"))
      (node (ref "U7") (pin "2") (pinfunction "VOUT_2") (pintype "output"))
      (node (ref "U7") (pin "4") (pinfunction "VOUT_4") (pintype "output"))
    )
    (net (code "4") (name "+3V3_3") (class "Default")
      (node (ref "C32") (pin "1") (pinfunction "1_1") (pintype "passive"))
      (node (ref "C50") (pin "1") (pinfunction "1_1") (pintype "passive"))
      (node (ref "C54") (pin "1") (pinfunction "1_1") (pintype "passive"))
      (node (ref "C55") (pin "1") (pinfunction "1_1") (pintype "passive"))
      (node (ref "C65") (pin "+") (pinfunction "+_+") (pintype "passive"))
      (node (ref "C69") (pin "1") (pinfunction "1_1") (pintype "passive"))
      (node (ref "IC10") (pin "18") (pinfunction "VCC_18") (pintype "power_in"))
      (node (ref "IC10") (pin "6") (pinfunction "/RST_6") (pintype "input"))
      (node (ref "IC8") (pin "5") (pinfunction "VCC_5") (pintype "power_in"))
      (node (ref "IC9") (pin "5") (pinfunction "VCC_5") (pintype "power_in"))
      (node (ref "J5") (pin "6") (pinfunction "6_6") (pintype "passive"))
      (node (ref "JP10") (pin "2") (pinfunction "2_2") (pintype "passive"))
      (node (ref "JP12") (pin "6") (pinfunction "6_6") (pintype "passive"))
      (node (ref "LED3") (pin "A") (pinfunction "A_A") (pintype "passive"))
      (node (ref "Q1") (pin "1") (pinfunction "G_1") (pintype "passive"))
      (node (ref "Q2") (pin "1") (pinfunction "G_1") (pintype "passive"))
      (node (ref "R14") (pin "2") (pinfunction "2_2") (pintype "passive"))
      (node (ref "R15") (pin "2") (pinfunction "2_2") (pintype "passive"))
      (node (ref "TP7") (pin "TP") (pinfunction "TP_TP") (pintype "input"))
      (node (ref "U2") (pin "16") (pinfunction "VCC_16") (pintype "bidirectional"))
      (node (ref "U8") (pin "2") (pinfunction "VOUT_2") (pintype "output"))
      (node (ref "U8") (pin "4") (pinfunction "VOUT_4") (pintype "output"))
    )
    (net (code "5") (name "+5V") (class "Default")
      (node (ref "C36") (pin "+") (pinfunction "+_+") (pintype "passive"))
      (node (ref "C62") (pin "+") (pinfunction "+_+") (pintype "passive"))
      (node (ref "C64") (pin "+") (pinfunction "+_+") (pintype "passive"))
      (node (ref "D3") (pin "A") (pinfunction "A_A") (pintype "passive"))
      (node (ref "J1") (pin "1") (pinfunction "1_1") (pintype "passive"))
      (node (ref "J1") (pin "2") (pinfunction "2_2") (pintype "passive"))
      (node (ref "JP13") (pin "2") (pinfunction "2_2") (pintype "passive"))
      (node (ref "JP14") (pin "2") (pinfunction "2_2") (pintype "passive"))
      (node (ref "JP15") (pin "2") (pinfunction "2_2") (pintype "passive"))
      (node (ref "JP2") (pin "1") (pinfunction "1_1") (pintype "passive"))
      (node (ref "JP8") (pin "3") (pinfunction "3_3") (pintype "passive"))
      (node (ref "TP2") (pin "TP") (pinfunction "TP_TP") (pintype "input"))
      (node (ref "U5") (pin "3") (pinfunction "VIN_3") (pintype "input"))
      (node (ref "U7") (pin "3") (pinfunction "VIN_3") (pintype "input"))
      (node (ref "U8") (pin "3") (pinfunction "VIN_3") (pintype "input"))
    )
    (net (code "6") (name "+12V") (class "Default")
      (node (ref "C37") (pin "+") (pinfunction "+_+") (pintype "passive"))
      (node (ref "C39") (pin "+") (pinfunction "+_+") (pintype "passive"))
      (node (ref "C66") (pin "2") (pinfunction "2_2") (pintype "passive"))
      (node (ref "IC11") (pin "4") (pinfunction "IN-_4") (pintype "input"))
      (node (ref "IC11") (pin "5") (pinfunction "V+_5") (pintype "power_in"))
      (node (ref "IC4") (pin "1") (pinfunction "VI_1") (pintype "input"))
      (node (ref "J17") (pin "2") (pinfunction "2_2") (pintype "passive"))
      (node (ref "R31") (pin "2") (pinfunction "2_2") (pintype "passive"))
      (node (ref "TP3") (pin "TP") (pinfunction "TP_TP") (pintype "input"))
    )
    (net (code "7") (name "/E3") (class "Default")
      (node (ref "IC1") (pin "3") (pinfunction "B1/1_3") (pintype "bidirectional"))
      (node (ref "J15") (pin "7") (pinfunction "7_7") (pintype "passive"))
    )
    (net (code "8") (name "/E4") (class "Default")
      (node (ref "IC1") (pin "4") (pinfunction "B1/2_4") (pintype "bidirectional"))
      (node (ref "J15") (pin "6") (pinfunction "6_6") (pintype "passive"))
    )
    (net (code "9") (name "/E5") (class "Default")
      (node (ref "IC1") (pin "5") (pinfunction "B1/3_5") (pintype "bidirectional"))
      (node (ref "J15") (pin "5") (pinfunction "5_5") (pintype "passive"))
    )
    (net (code "10") (name "/E6") (class "Default")
      (node (ref "IC1") (pin "6") (pinfunction "B1/4_6") (pintype "bidirectional"))
      (node (ref "J15") (pin "4") (pinfunction "4_4") (pintype "passive"))
    )
    (net (code "11") (name "/E7") (class "Default")
      (node (ref "IC1") (pin "7") (pinfunction "B1/5_7") (pintype "bidirectional"))
      (node (ref "J15") (pin "3") (pinfunction "3_3") (pintype "passive"))
    )
    (net (code "12") (name "/E8") (class "Default")
      (node (ref "IC1") (pin "8") (pinfunction "B1/6_8") (pintype "bidirectional"))
      (node (ref "J15") (pin "2") (pinfunction "2_2") (pintype "passive"))
    )
    (net (code "13") (name "/TCK") (class "Default")
      (node (ref "IC1") (pin "24") (pinfunction "B1/22-TCK_24") (pintype "input"))
      (node (ref "JP1") (pin "1") (pinfunction "1_1") (pintype "passive"))
      (node (ref "R38") (pin "2") (pinfunction "2_2") (pintype "passive"))
    )
    (net (code "14") (name "/TDI") (class "Default")
      (node (ref "IC1") (pin "23") (pinfunction "B1/21-TDI_23") (pintype "input"))
      (node (ref "JP1") (pin "9") (pinfunction "9_9") (pintype "passive"))
      (node (ref "R36") (pin "1") (pinfunction "1_1") (pintype "passive"))
    )
    (net (code "15") (name "/TDO") (class "Default")
      (node (ref "IC1") (pin "25") (pinfunction "B1/24-TDO_25") (pintype "output"))
      (node (ref "JP1") (pin "3") (pinfunction "3_3") (pintype "passive"))
      (node (ref "R35") (pin "1") (pinfunction "1_1") (pintype "passive"))
    )
    (net (code "16") (name "/TMS") (class "Default")
      (node (ref "IC1") (pin "22") (pinfunction "B1/20-TMS_22") (pintype "input"))
      (node (ref "JP1") (pin "5") (pinfunction "5_5") (pintype "passive"))
      (node (ref "R37") (pin "1") (pinfunction "1_1") (pintype "passive"))
    )
    (net (code "17") (name "0V") (class "Default")
      (node (ref "C1") (pin "2") (pinfunction "2_2") (pintype "passive"))
      (node (ref "C10") (pin "2") (pinfunction "2_2") (pintype "passive"))
      (node (ref "C11") (pin "2") (pinfunction "2_2") (pintype "passive"))
      (node (ref "C12") (pin "2") (pinfunction "2_2") (pintype "passive"))
      (node (ref "C14") (pin "2") (pinfunction "2_2") (pintype "passive"))
      (node (ref "C15") (pin "2") (pinfunction "2_2") (pintype "passive"))
      (node (ref "C16") (pin "2") (pinfunction "2_2") (pintype "passive"))
      (node (ref "C17") (pin "2") (pinfunction "2_2") (pintype "passive"))
      (node (ref "C18") (pin "2") (pinfunction "2_2") (pintype "passive"))
      (node (ref "C19") (pin "2") (pinfunction "2_2") (pintype "passive"))
      (node (ref "C2") (pin "2") (pinfunction "2_2") (pintype "passive"))
      (node (ref "C20") (pin "2") (pinfunction "2_2") (pintype "passive"))
      (node (ref "C21") (pin "2") (pinfunction "2_2") (pintype "passive"))
      (node (ref "C22") (pin "-") (pinfunction "-_-") (pintype "passive"))
      (node (ref "C23") (pin "1") (pinfunction "1_1") (pintype "passive"))
      (node (ref "C24") (pin "1") (pinfunction "1_1") (pintype "passive"))
      (node (ref "C26") (pin "2") (pinfunction "2_2") (pintype "passive"))
      (node (ref "C27") (pin "1") (pinfunction "1_1") (pintype "passive"))
      (node (ref "C28") (pin "2") (pinfunction "2_2") (pintype "passive"))
      (node (ref "C29") (pin "2") (pinfunction "2_2") (pintype "passive"))
      (node (ref "C3") (pin "2") (pinfunction "2_2") (pintype "passive"))
      (node (ref "C30") (pin "+") (pinfunction "+_+") (pintype "passive"))
      (node (ref "C32") (pin "2") (pinfunction "2_2") (pintype "passive"))
      (node (ref "C33") (pin "2") (pinfunction "2_2") (pintype "passive"))
      (node (ref "C34") (pin "2") (pinfunction "2_2") (pintype "passive"))
      (node (ref "C36") (pin "-") (pinfunction "-_-") (pintype "passive"))
      (node (ref "C37") (pin "-") (pinfunction "-_-") (pintype "passive"))
      (node (ref "C38") (pin "-") (pinfunction "-_-") (pintype "passive"))
      (node (ref "C39") (pin "-") (pinfunction "-_-") (pintype "passive"))
      (node (ref "C4") (pin "2") (pinfunction "2_2") (pintype "passive"))
      (node (ref "C42") (pin "2") (pinfunction "2_2") (pintype "passive"))
      (node (ref "C43") (pin "1") (pinfunction "1_1") (pintype "passive"))
      (node (ref "C44") (pin "2") (pinfunction "2_2") (pintype "passive"))
      (node (ref "C45") (pin "2") (pinfunction "2_2") (pintype "passive"))
      (node (ref "C48") (pin "2") (pinfunction "2_2") (pintype "passive"))
      (node (ref "C49") (pin "2") (pinfunction "2_2") (pintype "passive"))
      (node (ref "C5") (pin "2") (pinfunction "2_2") (pintype "passive"))
      (node (ref "C50") (pin "2") (pinfunction "2_2") (pintype "passive"))
      (node (ref "C51") (pin "1") (pinfunction "1_1") (pintype "passive"))
      (node (ref "C54") (pin "2") (pinfunction "2_2") (pintype "passive"))
      (node (ref "C55") (pin "2") (pinfunction "2_2") (pintype "passive"))
      (node (ref "C56") (pin "2") (pinfunction "2_2") (pintype "passive"))
      (node (ref "C57") (pin "2") (pinfunction "2_2") (pintype "passive"))
      (node (ref "C58") (pin "2") (pinfunction "2_2") (pintype "passive"))
      (node (ref "C59") (pin "2") (pinfunction "2_2") (pintype "passive"))
      (node (ref "C6") (pin "2") (pinfunction "2_2") (pintype "passive"))
      (node (ref "C62") (pin "-") (pinfunction "-_-") (pintype "passive"))
      (node (ref "C63") (pin "-") (pinfunction "-_-") (pintype "passive"))
      (node (ref "C64") (pin "-") (pinfunction "-_-") (pintype "passive"))
      (node (ref "C65") (pin "-") (pinfunction "-_-") (pintype "passive"))
      (node (ref "C67") (pin "2") (pinfunction "2_2") (pintype "passive"))
      (node (ref "C68") (pin "1") (pinfunction "1_1") (pintype "passive"))
      (node (ref "C69") (pin "2") (pinfunction "2_2") (pintype "passive"))
      (node (ref "C7") (pin "2") (pinfunction "2_2") (pintype "passive"))
      (node (ref "C70") (pin "-") (pinfunction "-_-") (pintype "passive"))
      (node (ref "C8") (pin "2") (pinfunction "2_2") (pintype "passive"))
      (node (ref "C9") (pin "2") (pinfunction "2_2") (pintype "passive"))
      (node (ref "D1") (pin "1") (pinfunction "A1_1") (pintype "passive"))
      (node (ref "D10") (pin "1") (pinfunction "A1_1") (pintype "passive"))
      (node (ref "D2") (pin "1") (pinfunction "A1_1") (pintype "passive"))
      (node (ref "D4") (pin "1") (pinfunction "A1_1") (pintype "passive"))
      (node (ref "D5") (pin "1") (pinfunction "A1_1") (pintype "passive"))
      (node (ref "D6") (pin "1") (pinfunction "A1_1") (pintype "passive"))
      (node (ref "D7") (pin "1") (pinfunction "A1_1") (pintype "passive"))
      (node (ref "D8") (pin "1") (pinfunction "A1_1") (pintype "passive"))
      (node (ref "D9") (pin "1") (pinfunction "A1_1") (pintype "passive"))
      (node (ref "IC1") (pin "10") (pinfunction "GNDIO_10") (pintype "power_in"))
      (node (ref "IC1") (pin "11") (pinfunction "GNDINT_11") (pintype "power_in"))
      (node (ref "IC1") (pin "17") (pinfunction "B1/15_17") (pintype "bidirectional"))
      (node (ref "IC1") (pin "21") (pinfunction "B1/19_21") (pintype "bidirectional"))
      (node (ref "IC1") (pin "32") (pinfunction "GNDIO_32") (pintype "power_in"))
      (node (ref "IC1") (pin "46") (pinfunction "GNDIO_46") (pintype "power_in"))
      (node (ref "IC1") (pin "50") (pinfunction "B1/49_50") (pintype "bidirectional"))
      (node (ref "IC1") (pin "56") (pinfunction "B2/55_56") (pintype "bidirectional"))
      (node (ref "IC1") (pin "58") (pinfunction "B2/57_58") (pintype "bidirectional"))
      (node (ref "IC1") (pin "60") (pinfunction "GNDIO_60") (pintype "power_in"))
      (node (ref "IC1") (pin "61") (pinfunction "B2/60_61") (pintype "bidirectional"))
      (node (ref "IC1") (pin "65") (pinfunction "GNDINT_65") (pintype "power_in"))
      (node (ref "IC1") (pin "66") (pinfunction "B2/65_66") (pintype "bidirectional"))
      (node (ref "IC1") (pin "70") (pinfunction "B2/69_70") (pintype "bidirectional"))
      (node (ref "IC1") (pin "71") (pinfunction "B2/70_71") (pintype "bidirectional"))
      (node (ref "IC1") (pin "74") (pinfunction "B2/73_74") (pintype "bidirectional"))
      (node (ref "IC1") (pin "75") (pinfunction "B2/74_75") (pintype "bidirectional"))
      (node (ref "IC1") (pin "79") (pinfunction "GNDIO_79") (pintype "power_in"))
      (node (ref "IC1") (pin "85") (pinfunction "B2/84_85") (pintype "bidirectional"))
      (node (ref "IC1") (pin "93") (pinfunction "GNDIO_93") (pintype "power_in"))
      (node (ref "IC1") (pin "95") (pinfunction "B2/94_95") (pintype "bidirectional"))
      (node (ref "IC10") (pin "4") (pinfunction "A1_4") (pintype "input"))
      (node (ref "IC10") (pin "9") (pinfunction "GND_9") (pintype "power_in"))
      (node (ref "IC11") (pin "2") (pinfunction "V-_2") (pintype "power_in"))
      (node (ref "IC12") (pin "3") (pinfunction "GND_3") (pintype "power_in"))
      (node (ref "IC14") (pin "2") (pinfunction "GND_2") (pintype "passive"))
      (node (ref "IC14") (pin "4") (pinfunction "GND_4") (pintype "passive"))
      (node (ref "IC2") (pin "3") (pinfunction "GND_3") (pintype "power_in"))
      (node (ref "IC4") (pin "2") (pinfunction "GND_2") (pintype "passive"))
      (node (ref "IC4") (pin "4") (pinfunction "GND_4") (pintype "passive"))
      (node (ref "IC5") (pin "3") (pinfunction "GND_3") (pintype "power_in"))
      (node (ref "IC6") (pin "2") (pinfunction "V-_2") (pintype "power_in"))
      (node (ref "IC8") (pin "3") (pinfunction "GND_3") (pintype "power_in"))
      (node (ref "IC9") (pin "3") (pinfunction "GND_3") (pintype "power_in"))
      (node (ref "J1") (pin "10") (pinfunction "10_10") (pintype "passive"))
      (node (ref "J1") (pin "13") (pinfunction "13_13") (pintype "passive"))
      (node (ref "J1") (pin "14") (pinfunction "14_14") (pintype "passive"))
      (node (ref "J10") (pin "1") (pinfunction "1_1") (pintype "passive"))
      (node (ref "J13") (pin "1") (pinfunction "1_1") (pintype "passive"))
      (node (ref "J14") (pin "1") (pinfunction "1_1") (pintype "passive"))
      (node (ref "J15") (pin "1") (pinfunction "1_1") (pintype "passive"))
      (node (ref "J17") (pin "1") (pinfunction "1_1") (pintype "passive"))
      (node (ref "J19") (pin "2") (pinfunction "2_2") (pintype "passive"))
      (node (ref "J2") (pin "2") (pinfunction "2_2") (pintype "passive"))
      (node (ref "J3") (pin "1") (pinfunction "1_1") (pintype "passive"))
      (node (ref "J4") (pin "1") (pinfunction "1_1") (pintype "passive"))
      (node (ref "J5") (pin "2") (pinfunction "2_2") (pintype "passive"))
      (node (ref "J5") (pin "4") (pinfunction "4_4") (pintype "passive"))
      (node (ref "J5") (pin "9") (pinfunction "9_9") (pintype "passive"))
      (node (ref "J6") (pin "5") (pinfunction "5_5") (pintype "passive"))
      (node (ref "J6") (pin "6") (pinfunction "6_6") (pintype "passive"))
      (node (ref "J7") (pin "1") (pinfunction "1_1") (pintype "passive"))
      (node (ref "J8") (pin "1") (pinfunction "1_1") (pintype "passive"))
      (node (ref "JP1") (pin "10") (pinfunction "10_10") (pintype "passive"))
      (node (ref "JP1") (pin "2") (pinfunction "2_2") (pintype "passive"))
      (node (ref "JP11") (pin "5") (pinfunction "5_5") (pintype "passive"))
      (node (ref "JP12") (pin "1") (pinfunction "1_1") (pintype "passive"))
      (node (ref "JP13") (pin "1") (pinfunction "1_1") (pintype "passive"))
      (node (ref "JP14") (pin "1") (pinfunction "1_1") (pintype "passive"))
      (node (ref "JP15") (pin "1") (pinfunction "1_1") (pintype "passive"))
      (node (ref "JP16") (pin "1") (pinfunction "1_1") (pintype "passive"))
      (node (ref "JP5") (pin "5") (pinfunction "5_5") (pintype "passive"))
      (node (ref "JP9") (pin "1") (pinfunction "1_1") (pintype "passive"))
      (node (ref "R1") (pin "1") (pinfunction "1_1") (pintype "passive"))
      (node (ref "R18") (pin "1") (pinfunction "1_1") (pintype "passive"))
      (node (ref "R20") (pin "1") (pinfunction "1_1") (pintype "passive"))
      (node (ref "R21") (pin "1") (pinfunction "1_1") (pintype "passive"))
      (node (ref "R22") (pin "1") (pinfunction "1_1") (pintype "passive"))
      (node (ref "R23") (pin "1") (pinfunction "1_1") (pintype "passive"))
      (node (ref "R24") (pin "1") (pinfunction "1_1") (pintype "passive"))
      (node (ref "R29") (pin "1") (pinfunction "1_1") (pintype "passive"))
      (node (ref "R34") (pin "2") (pinfunction "2_2") (pintype "passive"))
      (node (ref "R38") (pin "1") (pinfunction "1_1") (pintype "passive"))
      (node (ref "R39") (pin "2") (pinfunction "2_2") (pintype "passive"))
      (node (ref "R40") (pin "1") (pinfunction "1_1") (pintype "passive"))
      (node (ref "R42") (pin "1") (pinfunction "1_1") (pintype "passive"))
      (node (ref "R47") (pin "2") (pinfunction "2_2") (pintype "passive"))
      (node (ref "R51") (pin "1") (pinfunction "1_1") (pintype "passive"))
      (node (ref "R52") (pin "2") (pinfunction "2_2") (pintype "passive"))
      (node (ref "R53") (pin "1") (pinfunction "1_1") (pintype "passive"))
      (node (ref "R54") (pin "1") (pinfunction "1_1") (pintype "passive"))
      (node (ref "R7") (pin "1") (pinfunction "1_1") (pintype "passive"))
      (node (ref "S1") (pin "P1") (pinfunction "P$1_P1") (pintype "bidirectional"))
      (node (ref "S11") (pin "P1") (pinfunction "P$1_P1") (pintype "bidirectional"))
      (node (ref "S12") (pin "P1") (pinfunction "P$1_P1") (pintype "bidirectional"))
      (node (ref "S13") (pin "P1") (pinfunction "P$1_P1") (pintype "bidirectional"))
      (node (ref "S14") (pin "P1") (pinfunction "P$1_P1") (pintype "bidirectional"))
      (node (ref "S2") (pin "P1") (pinfunction "P$1_P1") (pintype "bidirectional"))
      (node (ref "T2") (pin "E") (pinfunction "E_E") (pintype "passive"))
      (node (ref "TP20") (pin "TP") (pinfunction "TP_TP") (pintype "input"))
      (node (ref "U$1") (pin "4") (pinfunction "GND_4") (pintype "bidirectional"))
      (node (ref "U$2") (pin "4") (pinfunction "GND_4") (pintype "bidirectional"))
      (node (ref "U1") (pin "2") (pinfunction "GND_2") (pintype "bidirectional"))
      (node (ref "U2") (pin "15") (pinfunction "GND_15") (pintype "bidirectional"))
      (node (ref "U3") (pin "2") (pinfunction "GND_2") (pintype "passive"))
      (node (ref "U4") (pin "3") (pinfunction "GND_3") (pintype "passive"))
      (node (ref "U4") (pin "6") (pinfunction "LV_6") (pintype "input"))
      (node (ref "U5") (pin "1") (pinfunction "GND_1") (pintype "passive"))
      (node (ref "U6") (pin "3") (pinfunction "+IN_3") (pintype "input"))
      (node (ref "U7") (pin "1") (pinfunction "GND_1") (pintype "passive"))
      (node (ref "U8") (pin "1") (pinfunction "GND_1") (pintype "passive"))
      (node (ref "U9") (pin "4") (pinfunction "GND_4") (pintype "bidirectional"))
      (node (ref "U9") (pin "7") (pinfunction "~{SYNC}/A0_7") (pintype "bidirectional"))
      (node (ref "X1") (pin "2") (pinfunction "2_2") (pintype "passive"))
      (node (ref "X2") (pin "3") (pinfunction "GND_3") (pintype "bidirectional"))
      (node (ref "X3") (pin "2") (pinfunction "2_2") (pintype "passive"))
      (node (ref "X3") (pin "3") (pinfunction "2_3") (pintype "passive"))
      (node (ref "X3") (pin "4") (pinfunction "2_4") (pintype "passive"))
      (node (ref "X3") (pin "5") (pinfunction "2_5") (pintype "passive"))
      (node (ref "X4") (pin "22") (pinfunction "1_22") (pintype "passive"))
      (node (ref "X5") (pin "2") (pinfunction "1_2") (pintype "passive"))
      (node (ref "X6") (pin "2") (pinfunction "2_2") (pintype "passive"))
      (node (ref "X7") (pin "2") (pinfunction "2_2") (pintype "passive"))
      (node (ref "X7") (pin "3") (pinfunction "2_3") (pintype "passive"))
      (node (ref "X7") (pin "4") (pinfunction "2_4") (pintype "passive"))
      (node (ref "X7") (pin "5") (pinfunction "2_5") (pintype "passive"))
      (node (ref "X8") (pin "2") (pinfunction "2_2") (pintype "passive"))
    )
    (net (code "18") (name "5V0") (class "Default")
      (node (ref "C24") (pin "2") (pinfunction "2_2") (pintype "passive"))
      (node (ref "C26") (pin "1") (pinfunction "1_1") (pintype "passive"))
      (node (ref "C51") (pin "2") (pinfunction "2_2") (pintype "passive"))
      (node (ref "C70") (pin "+") (pinfunction "+_+") (pintype "passive"))
      (node (ref "IC14") (pin "3") (pinfunction "VO_3") (pintype "passive"))
      (node (ref "L3") (pin "1") (pinfunction "1_1") (pintype "passive"))
      (node (ref "U3") (pin "1") (pinfunction "VIN_1") (pintype "power_in"))
      (node (ref "U3") (pin "3") (pinfunction "ON/OFF_3") (pintype "input"))
      (node (ref "U9") (pin "1") (pinfunction "VCC_1") (pintype "bidirectional"))
      (node (ref "U9") (pin "5") (pinfunction "SPI2C_5") (pintype "bidirectional"))
    )
    (net (code "19") (name "10MHZ") (class "Default")
      (node (ref "IC1") (pin "72") (pinfunction "B2/71_72") (pintype "bidirectional"))
      (node (ref "R17") (pin "1") (pinfunction "1_1") (pintype "passive"))
      (node (ref "R23") (pin "2") (pinfunction "2_2") (pintype "passive"))
      (node (ref "TP5") (pin "TP") (pinfunction "TP_TP") (pintype "input"))
    )
    (net (code "20") (name "B_CS") (class "Default")
      (node (ref "D8") (pin "3") (pinfunction "K1A2_3") (pintype "passive"))
      (node (ref "R49") (pin "1") (pinfunction "1_1") (pintype "passive"))
      (node (ref "X5") (pin "5") (pinfunction "1_5") (pintype "passive"))
    )
    (net (code "21") (name "CNT_CLR") (class "Default")
      (node (ref "IC1") (pin "40") (pinfunction "B1/39_40") (pintype "bidirectional"))
      (node (ref "X5") (pin "21") (pinfunction "1_21") (pintype "passive"))
    )
    (net (code "22") (name "CS") (class "Default")
      (node (ref "J1") (pin "3") (pinfunction "3_3") (pintype "passive"))
      (node (ref "X5") (pin "11") (pinfunction "1_11") (pintype "passive"))
    )
    (net (code "23") (name "DEV_CLRN") (class "Default")
      (node (ref "IC1") (pin "44") (pinfunction "B1/43-DEV_CLRN_44") (pintype "bidirectional"))
      (node (ref "X4") (pin "20") (pinfunction "1_20") (pintype "passive"))
    )
    (net (code "24") (name "DEV_OE") (class "Default")
      (node (ref "IC1") (pin "43") (pinfunction "B1/42-DEV_OE_43") (pintype "bidirectional"))
      (node (ref "X4") (pin "19") (pinfunction "1_19") (pintype "passive"))
    )
    (net (code "25") (name "E1") (class "Default")
      (node (ref "IC1") (pin "1") (pinfunction "B2/100_1") (pintype "bidirectional"))
      (node (ref "J15") (pin "9") (pinfunction "9_9") (pintype "passive"))
      (node (ref "X5") (pin "18") (pinfunction "1_18") (pintype "passive"))
    )
    (net (code "26") (name "E2") (class "Default")
      (node (ref "IC1") (pin "2") (pinfunction "B1/0_2") (pintype "bidirectional"))
      (node (ref "J15") (pin "8") (pinfunction "8_8") (pintype "passive"))
      (node (ref "X5") (pin "19") (pinfunction "1_19") (pintype "passive"))
    )
    (net (code "27") (name "E_RX") (class "Default")
      (node (ref "J7") (pin "3") (pinfunction "3_3") (pintype "passive"))
      (node (ref "JP6") (pin "3") (pinfunction "3_3") (pintype "passive"))
      (node (ref "X4") (pin "16") (pinfunction "1_16") (pintype "passive"))
    )
    (net (code "28") (name "E_TX") (class "Default")
      (node (ref "J7") (pin "2") (pinfunction "2_2") (pintype "passive"))
      (node (ref "JP7") (pin "3") (pinfunction "3_3") (pintype "passive"))
      (node (ref "X4") (pin "15") (pinfunction "1_15") (pintype "passive"))
    )
    (net (code "29") (name "GPS_RX") (class "Default")
      (node (ref "J19") (pin "3") (pinfunction "3_3") (pintype "passive"))
      (node (ref "J4") (pin "2") (pinfunction "2_2") (pintype "passive"))
      (node (ref "JP3") (pin "2") (pinfunction "2_2") (pintype "passive"))
      (node (ref "JP4") (pin "2") (pinfunction "2_2") (pintype "passive"))
      (node (ref "JP6") (pin "1") (pinfunction "1_1") (pintype "passive"))
    )
    (net (code "30") (name "GPS_TX") (class "Default")
      (node (ref "J1") (pin "7") (pinfunction "7_7") (pintype "passive"))
      (node (ref "J19") (pin "5") (pinfunction "5_5") (pintype "passive"))
      (node (ref "J4") (pin "3") (pinfunction "3_3") (pintype "passive"))
      (node (ref "JP7") (pin "1") (pinfunction "1_1") (pintype "passive"))
      (node (ref "X4") (pin "7") (pinfunction "1_7") (pintype "passive"))
    )
    (net (code "31") (name "INT") (class "Default")
      (node (ref "IC10") (pin "8") (pinfunction "INT_8") (pintype "output"))
      (node (ref "X4") (pin "21") (pinfunction "1_21") (pintype "passive"))
    )
    (net (code "32") (name "IVS") (class "Default")
      (node (ref "C57") (pin "1") (pinfunction "1_1") (pintype "passive"))
      (node (ref "R41") (pin "1") (pinfunction "1_1") (pintype "passive"))
      (node (ref "R42") (pin "2") (pinfunction "2_2") (pintype "passive"))
      (node (ref "X4") (pin "6") (pinfunction "1_6") (pintype "passive"))
    )
    (net (code "33") (name "MISO") (class "Default")
      (node (ref "D1") (pin "3") (pinfunction "K1A2_3") (pintype "passive"))
      (node (ref "J1") (pin "6") (pinfunction "6_6") (pintype "passive"))
      (node (ref "R33") (pin "1") (pinfunction "1_1") (pintype "passive"))
      (node (ref "X5") (pin "9") (pinfunction "1_9") (pintype "passive"))
    )
    (net (code "34") (name "MOSI") (class "Default")
      (node (ref "D7") (pin "3") (pinfunction "K1A2_3") (pintype "passive"))
      (node (ref "J1") (pin "5") (pinfunction "5_5") (pintype "passive"))
      (node (ref "R48") (pin "1") (pinfunction "1_1") (pintype "passive"))
      (node (ref "X5") (pin "8") (pinfunction "1_8") (pintype "passive"))
    )
    (net (code "35") (name "Net-(C18-Pad1)") (class "Default")
      (node (ref "C18") (pin "1") (pinfunction "1_1") (pintype "passive"))
      (node (ref "J19") (pin "7") (pinfunction "7_7") (pintype "passive"))
      (node (ref "JP2") (pin "2") (pinfunction "2_2") (pintype "passive"))
    )
    (net (code "36") (name "Net-(C66-Pad1)") (class "Default")
      (node (ref "C66") (pin "1") (pinfunction "1_1") (pintype "passive"))
      (node (ref "C67") (pin "1") (pinfunction "1_1") (pintype "passive"))
    )
    (net (code "37") (name "Net-(C68-Pad2)") (class "Default")
      (node (ref "C68") (pin "2") (pinfunction "2_2") (pintype "passive"))
      (node (ref "L3") (pin "2") (pinfunction "2_2") (pintype "passive"))
      (node (ref "R12") (pin "2") (pinfunction "2_2") (pintype "passive"))
      (node (ref "R13") (pin "2") (pinfunction "2_2") (pintype "passive"))
    )
    (net (code "38") (name "Net-(D3-PadC)") (class "Default")
      (node (ref "D3") (pin "C") (pinfunction "C_C") (pintype "passive"))
      (node (ref "X5") (pin "1") (pinfunction "1_1") (pintype "passive"))
    )
    (net (code "39") (name "Net-(D4-K1A2)") (class "Default")
      (node (ref "D4") (pin "3") (pinfunction "K1A2_3") (pintype "passive"))
      (node (ref "R2") (pin "1") (pinfunction "1_1") (pintype "passive"))
      (node (ref "U$1") (pin "1") (pinfunction "REF_1") (pintype "bidirectional"))
    )
    (net (code "40") (name "Net-(D6-K1A2)") (class "Default")
      (node (ref "D6") (pin "3") (pinfunction "K1A2_3") (pintype "passive"))
      (node (ref "J3") (pin "3") (pinfunction "3_3") (pintype "passive"))
      (node (ref "R45") (pin "1") (pinfunction "1_1") (pintype "passive"))
    )
    (net (code "41") (name "Net-(D10-K1A2)") (class "Default")
      (node (ref "D10") (pin "3") (pinfunction "K1A2_3") (pintype "passive"))
      (node (ref "J3") (pin "2") (pinfunction "2_2") (pintype "passive"))
      (node (ref "R57") (pin "1") (pinfunction "1_1") (pintype "passive"))
    )
    (net (code "42") (name "Net-(FB1-Pad1)") (class "Default")
      (node (ref "FB1") (pin "1") (pinfunction "1_1") (pintype "passive"))
      (node (ref "J6") (pin "2") (pinfunction "2_2") (pintype "passive"))
    )
    (net (code "43") (name "Net-(FB1-Pad2)") (class "Default")
      (node (ref "FB1") (pin "2") (pinfunction "2_2") (pintype "passive"))
      (node (ref "R48") (pin "2") (pinfunction "2_2") (pintype "passive"))
    )
    (net (code "44") (name "Net-(FB2-Pad1)") (class "Default")
      (node (ref "FB2") (pin "1") (pinfunction "1_1") (pintype "passive"))
      (node (ref "J6") (pin "4") (pinfunction "4_4") (pintype "passive"))
    )
    (net (code "45") (name "Net-(FB2-Pad2)") (class "Default")
      (node (ref "FB2") (pin "2") (pinfunction "2_2") (pintype "passive"))
      (node (ref "R49") (pin "2") (pinfunction "2_2") (pintype "passive"))
    )
    (net (code "46") (name "Net-(FB3-Pad1)") (class "Default")
      (node (ref "FB3") (pin "1") (pinfunction "1_1") (pintype "passive"))
      (node (ref "J6") (pin "8") (pinfunction "8_8") (pintype "passive"))
    )
    (net (code "47") (name "Net-(FB3-Pad2)") (class "Default")
      (node (ref "FB3") (pin "2") (pinfunction "2_2") (pintype "passive"))
      (node (ref "R50") (pin "2") (pinfunction "2_2") (pintype "passive"))
    )
    (net (code "48") (name "Net-(FB4-Pad1)") (class "Default")
      (node (ref "FB4") (pin "1") (pinfunction "1_1") (pintype "passive"))
      (node (ref "J6") (pin "10") (pinfunction "10_10") (pintype "passive"))
    )
    (net (code "49") (name "Net-(FB4-Pad2)") (class "Default")
      (node (ref "FB4") (pin "2") (pinfunction "2_2") (pintype "passive"))
      (node (ref "R57") (pin "2") (pinfunction "2_2") (pintype "passive"))
    )
    (net (code "50") (name "Net-(FB5-Pad1)") (class "Default")
      (node (ref "FB5") (pin "1") (pinfunction "1_1") (pintype "passive"))
      (node (ref "R33") (pin "2") (pinfunction "2_2") (pintype "passive"))
    )
    (net (code "51") (name "Net-(FB5-Pad2)") (class "Default")
      (node (ref "FB5") (pin "2") (pinfunction "2_2") (pintype "passive"))
      (node (ref "J6") (pin "1") (pinfunction "1_1") (pintype "passive"))
    )
    (net (code "52") (name "Net-(FB6-Pad1)") (class "Default")
      (node (ref "FB6") (pin "1") (pinfunction "1_1") (pintype "passive"))
      (node (ref "R43") (pin "2") (pinfunction "2_2") (pintype "passive"))
    )
    (net (code "53") (name "Net-(FB6-Pad2)") (class "Default")
      (node (ref "FB6") (pin "2") (pinfunction "2_2") (pintype "passive"))
      (node (ref "J6") (pin "3") (pinfunction "3_3") (pintype "passive"))
    )
    (net (code "54") (name "Net-(FB7-Pad1)") (class "Default")
      (node (ref "FB7") (pin "1") (pinfunction "1_1") (pintype "passive"))
      (node (ref "R44") (pin "2") (pinfunction "2_2") (pintype "passive"))
    )
    (net (code "55") (name "Net-(FB7-Pad2)") (class "Default")
      (node (ref "FB7") (pin "2") (pinfunction "2_2") (pintype "passive"))
      (node (ref "J6") (pin "7") (pinfunction "7_7") (pintype "passive"))
    )
    (net (code "56") (name "Net-(FB8-Pad1)") (class "Default")
      (node (ref "FB8") (pin "1") (pinfunction "1_1") (pintype "passive"))
      (node (ref "R45") (pin "2") (pinfunction "2_2") (pintype "passive"))
    )
    (net (code "57") (name "Net-(FB8-Pad2)") (class "Default")
      (node (ref "FB8") (pin "2") (pinfunction "2_2") (pintype "passive"))
      (node (ref "J6") (pin "9") (pinfunction "9_9") (pintype "passive"))
    )
    (net (code "58") (name "Net-(IC1-B1{slash}10-GCLK0)") (class "Default")
      (node (ref "IC1") (pin "12") (pinfunction "B1/10-GCLK0_12") (pintype "bidirectional"))
      (node (ref "U1") (pin "3") (pinfunction "OUT_3") (pintype "bidirectional"))
    )
    (net (code "59") (name "Net-(IC1-B2{slash}51)") (class "Default")
      (node (ref "IC1") (pin "52") (pinfunction "B2/51_52") (pintype "bidirectional"))
      (node (ref "R25") (pin "2") (pinfunction "2_2") (pintype "passive"))
    )
    (net (code "60") (name "Net-(IC1-B2{slash}52)") (class "Default")
      (node (ref "IC1") (pin "53") (pinfunction "B2/52_53") (pintype "bidirectional"))
      (node (ref "R26") (pin "2") (pinfunction "2_2") (pintype "passive"))
    )
    (net (code "61") (name "Net-(IC1-B2{slash}53)") (class "Default")
      (node (ref "IC1") (pin "54") (pinfunction "B2/53_54") (pintype "bidirectional"))
      (node (ref "R27") (pin "2") (pinfunction "2_2") (pintype "passive"))
    )
    (net (code "62") (name "Net-(IC1-B2{slash}54)") (class "Default")
      (node (ref "IC1") (pin "55") (pinfunction "B2/54_55") (pintype "bidirectional"))
      (node (ref "R28") (pin "2") (pinfunction "2_2") (pintype "passive"))
    )
    (net (code "63") (name "Net-(IC2A-O)") (class "Default")
      (node (ref "IC2") (pin "4") (pinfunction "O_4") (pintype "output"))
      (node (ref "R10") (pin "1") (pinfunction "1_1") (pintype "passive"))
      (node (ref "R19") (pin "1") (pinfunction "1_1") (pintype "passive"))
    )
    (net (code "64") (name "Net-(IC5A-I)") (class "Default")
      (node (ref "IC5") (pin "2") (pinfunction "I_2") (pintype "input"))
      (node (ref "R5") (pin "1") (pinfunction "1_1") (pintype "passive"))
      (node (ref "R52") (pin "1") (pinfunction "1_1") (pintype "passive"))
      (node (ref "X3") (pin "1") (pinfunction "1_1") (pintype "passive"))
    )
    (net (code "65") (name "Net-(IC5A-O)") (class "Default")
      (node (ref "IC5") (pin "4") (pinfunction "O_4") (pintype "output"))
      (node (ref "R3") (pin "1") (pinfunction "1_1") (pintype "passive"))
    )
    (net (code "66") (name "Net-(IC5B-VCC)") (class "Default")
      (node (ref "C59") (pin "1") (pinfunction "1_1") (pintype "passive"))
      (node (ref "IC5") (pin "5") (pinfunction "VCC_5") (pintype "power_in"))
      (node (ref "JP16") (pin "2") (pinfunction "2_2") (pintype "passive"))
    )
    (net (code "67") (name "Net-(IC6-+IN)") (class "Default")
      (node (ref "C43") (pin "2") (pinfunction "2_2") (pintype "passive"))
      (node (ref "IC6") (pin "3") (pinfunction "+IN_3") (pintype "input"))
      (node (ref "U9") (pin "2") (pinfunction "VOUT_2") (pintype "bidirectional"))
    )
    (net (code "68") (name "Net-(IC6--IN)") (class "Default")
      (node (ref "IC6") (pin "4") (pinfunction "-IN_4") (pintype "input"))
      (node (ref "R11") (pin "1") (pinfunction "1_1") (pintype "passive"))
      (node (ref "R20") (pin "2") (pinfunction "2_2") (pintype "passive"))
    )
    (net (code "69") (name "Net-(IC6-OUT)") (class "Default")
      (node (ref "C23") (pin "2") (pinfunction "2_2") (pintype "passive"))
      (node (ref "IC6") (pin "1") (pinfunction "OUT_1") (pintype "output"))
      (node (ref "R11") (pin "2") (pinfunction "2_2") (pintype "passive"))
      (node (ref "X2") (pin "4") (pinfunction "VADJ_4") (pintype "bidirectional"))
    )
    (net (code "70") (name "Net-(IC8A-I)") (class "Default")
      (node (ref "IC8") (pin "2") (pinfunction "I_2") (pintype "input"))
      (node (ref "R29") (pin "2") (pinfunction "2_2") (pintype "passive"))
      (node (ref "R32") (pin "2") (pinfunction "2_2") (pintype "passive"))
      (node (ref "R8") (pin "1") (pinfunction "1_1") (pintype "passive"))
    )
    (net (code "71") (name "Net-(IC10-A0)") (class "Default")
      (node (ref "IC10") (pin "5") (pinfunction "A0_5") (pintype "input"))
      (node (ref "R34") (pin "1") (pinfunction "1_1") (pintype "passive"))
    )
    (net (code "72") (name "Net-(IC10-A2)") (class "Default")
      (node (ref "IC10") (pin "3") (pinfunction "A2_3") (pintype "input"))
      (node (ref "R39") (pin "1") (pinfunction "1_1") (pintype "passive"))
    )
    (net (code "73") (name "Net-(IC10-GP0)") (class "Default")
      (node (ref "IC10") (pin "10") (pinfunction "GP0_10") (pintype "bidirectional"))
      (node (ref "J5") (pin "5") (pinfunction "5_5") (pintype "passive"))
    )
    (net (code "74") (name "Net-(IC10-GP1)") (class "Default")
      (node (ref "IC10") (pin "11") (pinfunction "GP1_11") (pintype "bidirectional"))
      (node (ref "J5") (pin "7") (pinfunction "7_7") (pintype "passive"))
    )
    (net (code "75") (name "Net-(IC10-GP2)") (class "Default")
      (node (ref "IC10") (pin "12") (pinfunction "GP2_12") (pintype "bidirectional"))
      (node (ref "J5") (pin "10") (pinfunction "10_10") (pintype "passive"))
    )
    (net (code "76") (name "Net-(IC10-GP3)") (class "Default")
      (node (ref "IC10") (pin "13") (pinfunction "GP3_13") (pintype "bidirectional"))
      (node (ref "J5") (pin "8") (pinfunction "8_8") (pintype "passive"))
    )
    (net (code "77") (name "Net-(IC10-GP4)") (class "Default")
      (node (ref "IC10") (pin "14") (pinfunction "GP4_14") (pintype "bidirectional"))
      (node (ref "JP12") (pin "5") (pinfunction "5_5") (pintype "passive"))
    )
    (net (code "78") (name "Net-(IC10-GP5)") (class "Default")
      (node (ref "IC10") (pin "15") (pinfunction "GP5_15") (pintype "bidirectional"))
      (node (ref "JP12") (pin "4") (pinfunction "4_4") (pintype "passive"))
    )
    (net (code "79") (name "Net-(IC10-GP6)") (class "Default")
      (node (ref "IC10") (pin "16") (pinfunction "GP6_16") (pintype "bidirectional"))
      (node (ref "JP12") (pin "3") (pinfunction "3_3") (pintype "passive"))
    )
    (net (code "80") (name "Net-(IC10-GP7)") (class "Default")
      (node (ref "IC10") (pin "17") (pinfunction "GP7_17") (pintype "bidirectional"))
      (node (ref "JP12") (pin "2") (pinfunction "2_2") (pintype "passive"))
    )
    (net (code "81") (name "Net-(IC11-IN+)") (class "Default")
      (node (ref "IC11") (pin "3") (pinfunction "IN+_3") (pintype "input"))
      (node (ref "R31") (pin "1") (pinfunction "1_1") (pintype "passive"))
      (node (ref "X2") (pin "1") (pinfunction "V+_1") (pintype "bidirectional"))
    )
    (net (code "82") (name "Net-(IC12A-I)") (class "Default")
      (node (ref "IC12") (pin "2") (pinfunction "I_2") (pintype "input"))
      (node (ref "IC2") (pin "2") (pinfunction "I_2") (pintype "input"))
      (node (ref "R46") (pin "1") (pinfunction "1_1") (pintype "passive"))
      (node (ref "R47") (pin "1") (pinfunction "1_1") (pintype "passive"))
    )
    (net (code "83") (name "Net-(IC12A-O)") (class "Default")
      (node (ref "IC12") (pin "4") (pinfunction "O_4") (pintype "output"))
      (node (ref "R4") (pin "1") (pinfunction "1_1") (pintype "passive"))
      (node (ref "R9") (pin "1") (pinfunction "1_1") (pintype "passive"))
    )
    (net (code "84") (name "Net-(IC12B-VCC)") (class "Default")
      (node (ref "C11") (pin "1") (pinfunction "1_1") (pintype "passive"))
      (node (ref "C12") (pin "1") (pinfunction "1_1") (pintype "passive"))
      (node (ref "C33") (pin "1") (pinfunction "1_1") (pintype "passive"))
      (node (ref "C34") (pin "1") (pinfunction "1_1") (pintype "passive"))
      (node (ref "IC12") (pin "5") (pinfunction "VCC_5") (pintype "power_in"))
      (node (ref "IC2") (pin "5") (pinfunction "VCC_5") (pintype "power_in"))
      (node (ref "JP8") (pin "2") (pinfunction "2_2") (pintype "passive"))
    )
    (net (code "85") (name "Net-(IC14-VI)") (class "Default")
      (node (ref "C22") (pin "+") (pinfunction "+_+") (pintype "passive"))
      (node (ref "C44") (pin "1") (pinfunction "1_1") (pintype "passive"))
      (node (ref "C45") (pin "1") (pinfunction "1_1") (pintype "passive"))
      (node (ref "IC14") (pin "1") (pinfunction "VI_1") (pintype "input"))
      (node (ref "IC4") (pin "3") (pinfunction "VO_3") (pintype "passive"))
      (node (ref "IC6") (pin "5") (pinfunction "V+_5") (pintype "power_in"))
    )
    (net (code "86") (name "Net-(J1-Pad8)") (class "Default")
      (node (ref "J1") (pin "8") (pinfunction "8_8") (pintype "passive"))
      (node (ref "JP4") (pin "1") (pinfunction "1_1") (pintype "passive"))
    )
    (net (code "87") (name "Net-(J2-Pad1)") (class "Default")
      (node (ref "J2") (pin "1") (pinfunction "1_1") (pintype "passive"))
      (node (ref "SW2") (pin "1") (pinfunction "1_1") (pintype "passive"))
    )
    (net (code "88") (name "Net-(J8-Pad2)") (class "Default")
      (node (ref "J8") (pin "2") (pinfunction "2_2") (pintype "passive"))
      (node (ref "R56") (pin "2") (pinfunction "2_2") (pintype "passive"))
    )
    (net (code "89") (name "Net-(J8-Pad3)") (class "Default")
      (node (ref "J8") (pin "3") (pinfunction "3_3") (pintype "passive"))
      (node (ref "R55") (pin "2") (pinfunction "2_2") (pintype "passive"))
    )
    (net (code "90") (name "Net-(JP5-Pad1)") (class "Default")
      (node (ref "JP5") (pin "1") (pinfunction "1_1") (pintype "passive"))
      (node (ref "SW2") (pin "4") (pinfunction "4_4") (pintype "passive"))
    )
    (net (code "91") (name "Net-(JP5-Pad6)") (class "Default")
      (node (ref "JP5") (pin "6") (pinfunction "6_6") (pintype "passive"))
      (node (ref "SW2") (pin "3") (pinfunction "3_3") (pintype "passive"))
    )
    (net (code "92") (name "Net-(JP5-Pad8)") (class "Default")
      (node (ref "JP5") (pin "8") (pinfunction "8_8") (pintype "passive"))
      (node (ref "SW2") (pin "2") (pinfunction "2_2") (pintype "passive"))
    )
    (net (code "93") (name "Net-(JP9-Pad2)") (class "Default")
      (node (ref "JP9") (pin "2") (pinfunction "2_2") (pintype "passive"))
      (node (ref "R41") (pin "2") (pinfunction "2_2") (pintype "passive"))
    )
    (net (code "94") (name "Net-(JP10-Pad1)") (class "Default")
      (node (ref "JP10") (pin "1") (pinfunction "1_1") (pintype "passive"))
      (node (ref "R30") (pin "2") (pinfunction "2_2") (pintype "passive"))
    )
    (net (code "95") (name "Net-(JP11-Pad1)") (class "Default")
      (node (ref "JP11") (pin "1") (pinfunction "1_1") (pintype "passive"))
      (node (ref "R28") (pin "1") (pinfunction "1_1") (pintype "passive"))
    )
    (net (code "96") (name "Net-(JP11-Pad2)") (class "Default")
      (node (ref "JP11") (pin "2") (pinfunction "2_2") (pintype "passive"))
      (node (ref "R27") (pin "1") (pinfunction "1_1") (pintype "passive"))
    )
    (net (code "97") (name "Net-(JP11-Pad3)") (class "Default")
      (node (ref "JP11") (pin "3") (pinfunction "3_3") (pintype "passive"))
      (node (ref "R26") (pin "1") (pinfunction "1_1") (pintype "passive"))
    )
    (net (code "98") (name "Net-(JP11-Pad4)") (class "Default")
      (node (ref "JP11") (pin "4") (pinfunction "4_4") (pintype "passive"))
      (node (ref "R25") (pin "1") (pinfunction "1_1") (pintype "passive"))
    )
    (net (code "99") (name "Net-(LED2-C)") (class "Default")
      (node (ref "LED2") (pin "K") (pinfunction "C_K") (pintype "passive"))
      (node (ref "R53") (pin "2") (pinfunction "2_2") (pintype "passive"))
    )
    (net (code "100") (name "Net-(LED3-C)") (class "Default")
      (node (ref "LED3") (pin "K") (pinfunction "C_K") (pintype "passive"))
      (node (ref "R54") (pin "2") (pinfunction "2_2") (pintype "passive"))
    )
    (net (code "101") (name "Net-(LED4-C)") (class "Default")
      (node (ref "LED4") (pin "K") (pinfunction "C_K") (pintype "passive"))
      (node (ref "R24") (pin "2") (pinfunction "2_2") (pintype "passive"))
    )
    (net (code "102") (name "Net-(Q1-D)") (class "Default")
      (node (ref "Q1") (pin "3") (pinfunction "D_3") (pintype "passive"))
      (node (ref "R13") (pin "1") (pinfunction "1_1") (pintype "passive"))
      (node (ref "U9") (pin "8") (pinfunction "SDIN/SDA_8") (pintype "bidirectional"))
    )
    (net (code "103") (name "Net-(Q2-D)") (class "Default")
      (node (ref "Q2") (pin "3") (pinfunction "D_3") (pintype "passive"))
      (node (ref "R12") (pin "1") (pinfunction "1_1") (pintype "passive"))
      (node (ref "U9") (pin "6") (pinfunction "SCLK/SCL_6") (pintype "bidirectional"))
    )
    (net (code "104") (name "Net-(R3-Pad2)") (class "Default")
      (node (ref "R3") (pin "2") (pinfunction "2_2") (pintype "passive"))
      (node (ref "X7") (pin "1") (pinfunction "1_1") (pintype "passive"))
    )
    (net (code "105") (name "Net-(R4-Pad2)") (class "Default")
      (node (ref "R4") (pin "2") (pinfunction "2_2") (pintype "passive"))
      (node (ref "R9") (pin "2") (pinfunction "2_2") (pintype "passive"))
      (node (ref "X8") (pin "1") (pinfunction "1_1") (pintype "passive"))
    )
    (net (code "106") (name "Net-(R10-Pad2)") (class "Default")
      (node (ref "R10") (pin "2") (pinfunction "2_2") (pintype "passive"))
      (node (ref "R19") (pin "2") (pinfunction "2_2") (pintype "passive"))
      (node (ref "X6") (pin "1") (pinfunction "1_1") (pintype "passive"))
    )
    (net (code "107") (name "Net-(R16-Pad1)") (class "Default")
      (node (ref "R16") (pin "1") (pinfunction "1_1") (pintype "passive"))
      (node (ref "X1") (pin "1") (pinfunction "1_1") (pintype "passive"))
    )
    (net (code "108") (name "Net-(R30-Pad1)") (class "Default")
      (node (ref "R30") (pin "1") (pinfunction "1_1") (pintype "passive"))
      (node (ref "T2") (pin "C") (pinfunction "C_C") (pintype "passive"))
    )
    (net (code "109") (name "Net-(R32-Pad1)") (class "Default")
      (node (ref "R32") (pin "1") (pinfunction "1_1") (pintype "passive"))
      (node (ref "T2") (pin "B") (pinfunction "B_B") (pintype "passive"))
    )
    (net (code "110") (name "Net-(U$1-CLK1)") (class "Default")
      (node (ref "R21") (pin "2") (pinfunction "2_2") (pintype "passive"))
      (node (ref "U$1") (pin "2") (pinfunction "CLK1_2") (pintype "bidirectional"))
    )
    (net (code "111") (name "Net-(U$1-CLK2)") (class "Default")
      (node (ref "R17") (pin "2") (pinfunction "2_2") (pintype "passive"))
      (node (ref "U$1") (pin "3") (pinfunction "CLK2_3") (pintype "bidirectional"))
    )
    (net (code "112") (name "Net-(U$1-CLK3)") (class "Default")
      (node (ref "R46") (pin "2") (pinfunction "2_2") (pintype "passive"))
      (node (ref "U$1") (pin "5") (pinfunction "CLK3_5") (pintype "bidirectional"))
    )
    (net (code "113") (name "Net-(U$1-CLK4)") (class "Default")
      (node (ref "R16") (pin "2") (pinfunction "2_2") (pintype "passive"))
      (node (ref "U$1") (pin "7") (pinfunction "CLK4_7") (pintype "bidirectional"))
    )
    (net (code "114") (name "Net-(U$1-CLK5)") (class "Default")
      (node (ref "R22") (pin "2") (pinfunction "2_2") (pintype "passive"))
      (node (ref "U$1") (pin "8") (pinfunction "CLK5_8") (pintype "bidirectional"))
    )
    (net (code "115") (name "Net-(U$2-CLK1)") (class "Default")
      (node (ref "R5") (pin "2") (pinfunction "2_2") (pintype "passive"))
      (node (ref "U$2") (pin "2") (pinfunction "CLK1_2") (pintype "bidirectional"))
    )
    (net (code "116") (name "Net-(U$2-CLK2)") (class "Default")
      (node (ref "R6") (pin "2") (pinfunction "2_2") (pintype "passive"))
      (node (ref "U$2") (pin "3") (pinfunction "CLK2_3") (pintype "bidirectional"))
    )
    (net (code "117") (name "Net-(U$2-CLK3)") (class "Default")
      (node (ref "R18") (pin "2") (pinfunction "2_2") (pintype "passive"))
      (node (ref "U$2") (pin "5") (pinfunction "CLK3_5") (pintype "bidirectional"))
    )
    (net (code "118") (name "Net-(U$2-CLK4)") (class "Default")
      (node (ref "R7") (pin "2") (pinfunction "2_2") (pintype "passive"))
      (node (ref "U$2") (pin "7") (pinfunction "CLK4_7") (pintype "bidirectional"))
    )
    (net (code "119") (name "Net-(U$2-CLK5)") (class "Default")
      (node (ref "R8") (pin "2") (pinfunction "2_2") (pintype "passive"))
      (node (ref "U$2") (pin "8") (pinfunction "CLK5_8") (pintype "bidirectional"))
    )
    (net (code "120") (name "Net-(U$2-REF)") (class "Default")
      (node (ref "J19") (pin "4") (pinfunction "4_4") (pintype "passive"))
      (node (ref "R51") (pin "2") (pinfunction "2_2") (pintype "passive"))
      (node (ref "U$2") (pin "1") (pinfunction "REF_1") (pintype "bidirectional"))
    )
    (net (code "121") (name "Net-(U2-C1+)") (class "Default")
      (node (ref "C46") (pin "2") (pinfunction "2_2") (pintype "passive"))
      (node (ref "U2") (pin "1") (pinfunction "C1+_1") (pintype "bidirectional"))
    )
    (net (code "122") (name "Net-(U2-C1-)") (class "Default")
      (node (ref "C46") (pin "1") (pinfunction "1_1") (pintype "passive"))
      (node (ref "U2") (pin "3") (pinfunction "C1-_3") (pintype "bidirectional"))
    )
    (net (code "123") (name "Net-(U2-C2+)") (class "Default")
      (node (ref "C47") (pin "2") (pinfunction "2_2") (pintype "passive"))
      (node (ref "U2") (pin "4") (pinfunction "C2+_4") (pintype "bidirectional"))
    )
    (net (code "124") (name "Net-(U2-C2-)") (class "Default")
      (node (ref "C47") (pin "1") (pinfunction "1_1") (pintype "passive"))
      (node (ref "U2") (pin "5") (pinfunction "C2-_5") (pintype "bidirectional"))
    )
    (net (code "125") (name "Net-(U2-R1IN)") (class "Default")
      (node (ref "JP6") (pin "2") (pinfunction "2_2") (pintype "passive"))
      (node (ref "R56") (pin "1") (pinfunction "1_1") (pintype "passive"))
      (node (ref "U2") (pin "13") (pinfunction "R1IN_13") (pintype "input"))
    )
    (net (code "126") (name "Net-(U2-R1OUT)") (class "Default")
      (node (ref "JP5") (pin "2") (pinfunction "2_2") (pintype "passive"))
      (node (ref "U2") (pin "12") (pinfunction "R1OUT_12") (pintype "output"))
    )
    (net (code "127") (name "Net-(U2-R2OUT)") (class "Default")
      (node (ref "SW2") (pin "5") (pinfunction "5_5") (pintype "passive"))
      (node (ref "SW2") (pin "6") (pinfunction "6_6") (pintype "passive"))
      (node (ref "SW2") (pin "7") (pinfunction "7_7") (pintype "passive"))
      (node (ref "SW2") (pin "8") (pinfunction "8_8") (pintype "passive"))
      (node (ref "U2") (pin "9") (pinfunction "R2OUT_9") (pintype "output"))
    )
    (net (code "128") (name "Net-(U2-T2IN)") (class "Default")
      (node (ref "JP5") (pin "3") (pinfunction "3_3") (pintype "passive"))
      (node (ref "U2") (pin "10") (pinfunction "T2IN_10") (pintype "input"))
    )
    (net (code "129") (name "Net-(U2-T2OUT)") (class "Default")
      (node (ref "JP7") (pin "2") (pinfunction "2_2") (pintype "passive"))
      (node (ref "R55") (pin "1") (pinfunction "1_1") (pintype "passive"))
      (node (ref "U2") (pin "7") (pinfunction "T2OUT_7") (pintype "output"))
    )
    (net (code "130") (name "Net-(U2-V+)") (class "Default")
      (node (ref "C49") (pin "1") (pinfunction "1_1") (pintype "passive"))
      (node (ref "U2") (pin "2") (pinfunction "V+_2") (pintype "bidirectional"))
    )
    (net (code "131") (name "Net-(U2-V-)") (class "Default")
      (node (ref "C48") (pin "1") (pinfunction "1_1") (pintype "passive"))
      (node (ref "U2") (pin "6") (pinfunction "V-_6") (pintype "bidirectional"))
    )
    (net (code "132") (name "Net-(U4-CAP+)") (class "Default")
      (node (ref "C41") (pin "+") (pinfunction "+_+") (pintype "passive"))
      (node (ref "U4") (pin "2") (pinfunction "CAP+_2") (pintype "input"))
    )
    (net (code "133") (name "Net-(U4-CAP-)") (class "Default")
      (node (ref "C41") (pin "-") (pinfunction "-_-") (pintype "passive"))
      (node (ref "U4") (pin "4") (pinfunction "CAP-_4") (pintype "input"))
    )
    (net (code "134") (name "Net-(U4-OUT)") (class "Default")
      (node (ref "C15") (pin "1") (pinfunction "1_1") (pintype "passive"))
      (node (ref "C16") (pin "1") (pinfunction "1_1") (pintype "passive"))
      (node (ref "C30") (pin "-") (pinfunction "-_-") (pintype "passive"))
      (node (ref "TP8") (pin "TP") (pinfunction "TP_TP") (pintype "input"))
      (node (ref "U4") (pin "5") (pinfunction "OUT_5") (pintype "output"))
      (node (ref "U6") (pin "2") (pinfunction "V-_2") (pintype "power_in"))
      (node (ref "U6") (pin "6") (pinfunction "SHDN_6") (pintype "input"))
    )
    (net (code "135") (name "Net-(U6--IN)") (class "Default")
      (node (ref "C13") (pin "2") (pinfunction "2_2") (pintype "passive"))
      (node (ref "U6") (pin "1") (pinfunction "-IN_1") (pintype "input"))
    )
    (net (code "136") (name "Net-(U6-OUT)") (class "Default")
      (node (ref "R2") (pin "2") (pinfunction "2_2") (pintype "passive"))
      (node (ref "U6") (pin "5") (pinfunction "OUT_5") (pintype "output"))
    )
    (net (code "137") (name "Net-(U9-VREF)") (class "Default")
      (node (ref "C27") (pin "2") (pinfunction "2_2") (pintype "passive"))
      (node (ref "U9") (pin "10") (pinfunction "VREF_10") (pintype "bidirectional"))
    )
    (net (code "138") (name "Net-(X2-OUT)") (class "Default")
      (node (ref "C13") (pin "1") (pinfunction "1_1") (pintype "passive"))
      (node (ref "X2") (pin "6") (pinfunction "OUT_6") (pintype "bidirectional"))
    )
    (net (code "139") (name "Net-(X4P-1)") (class "Default")
      (node (ref "J10") (pin "2") (pinfunction "2_2") (pintype "passive"))
      (node (ref "X4") (pin "3") (pinfunction "1_3") (pintype "passive"))
    )
    (net (code "140") (name "Net-(X4U-1)") (class "Default")
      (node (ref "JP3") (pin "1") (pinfunction "1_1") (pintype "passive"))
      (node (ref "X4") (pin "8") (pinfunction "1_8") (pintype "passive"))
    )
    (net (code "141") (name "Net-(X4V-1)") (class "Default")
      (node (ref "J13") (pin "2") (pinfunction "2_2") (pintype "passive"))
      (node (ref "X4") (pin "9") (pinfunction "1_9") (pintype "passive"))
    )
    (net (code "142") (name "Net-(X5M-1)") (class "Default")
      (node (ref "J14") (pin "2") (pinfunction "2_2") (pintype "passive"))
      (node (ref "X5") (pin "20") (pinfunction "1_20") (pintype "passive"))
    )
    (net (code "143") (name "OCXO_C") (class "Default")
      (node (ref "C56") (pin "1") (pinfunction "1_1") (pintype "passive"))
      (node (ref "IC11") (pin "1") (pinfunction "OUT_1") (pintype "output"))
      (node (ref "R40") (pin "2") (pinfunction "2_2") (pintype "passive"))
      (node (ref "X5") (pin "22") (pinfunction "1_22") (pintype "passive"))
    )
    (net (code "144") (name "PPS") (class "Default")
      (node (ref "IC1") (pin "78") (pinfunction "B2/77_78") (pintype "bidirectional"))
      (node (ref "R1") (pin "2") (pinfunction "2_2") (pintype "passive"))
      (node (ref "R6") (pin "1") (pinfunction "1_1") (pintype "passive"))
      (node (ref "TP4") (pin "TP") (pinfunction "TP_TP") (pintype "input"))
    )
    (net (code "145") (name "PPS_E") (class "Default")
      (node (ref "IC9") (pin "4") (pinfunction "O_4") (pintype "output"))
      (node (ref "J1") (pin "12") (pinfunction "12_12") (pintype "passive"))
      (node (ref "U2") (pin "8") (pinfunction "R2IN_8") (pintype "input"))
    )
    (net (code "146") (name "PPS_MCU") (class "Default")
      (node (ref "IC8") (pin "4") (pinfunction "O_4") (pintype "output"))
      (node (ref "IC9") (pin "2") (pinfunction "I_2") (pintype "input"))
      (node (ref "X5") (pin "17") (pinfunction "1_17") (pintype "passive"))
    )
    (net (code "147") (name "RDY") (class "Default")
      (node (ref "IC1") (pin "38") (pinfunction "B1/37_38") (pintype "bidirectional"))
      (node (ref "X5") (pin "13") (pinfunction "1_13") (pintype "passive"))
    )
    (net (code "148") (name "RUN") (class "Default")
      (node (ref "IC1") (pin "39") (pinfunction "B1/38_39") (pintype "bidirectional"))
      (node (ref "X5") (pin "14") (pinfunction "1_14") (pintype "passive"))
    )
    (net (code "149") (name "SCK") (class "Default")
      (node (ref "D2") (pin "3") (pinfunction "K1A2_3") (pintype "passive"))
      (node (ref "J1") (pin "4") (pinfunction "4_4") (pintype "passive"))
      (node (ref "R43") (pin "1") (pinfunction "1_1") (pintype "passive"))
      (node (ref "X5") (pin "10") (pinfunction "1_10") (pintype "passive"))
    )
    (net (code "150") (name "SCL") (class "Default")
      (node (ref "D5") (pin "3") (pinfunction "K1A2_3") (pintype "passive"))
      (node (ref "IC10") (pin "1") (pinfunction "SCL_1") (pintype "bidirectional"))
      (node (ref "J1") (pin "11") (pinfunction "11_11") (pintype "passive"))
      (node (ref "J5") (pin "3") (pinfunction "3_3") (pintype "passive"))
      (node (ref "Q2") (pin "2") (pinfunction "S_2") (pintype "passive"))
      (node (ref "R15") (pin "1") (pinfunction "1_1") (pintype "passive"))
      (node (ref "R44") (pin "1") (pinfunction "1_1") (pintype "passive"))
      (node (ref "X5") (pin "16") (pinfunction "1_16") (pintype "passive"))
    )
    (net (code "151") (name "SDA") (class "Default")
      (node (ref "D9") (pin "3") (pinfunction "K1A2_3") (pintype "passive"))
      (node (ref "IC10") (pin "2") (pinfunction "SDA_2") (pintype "bidirectional"))
      (node (ref "J1") (pin "9") (pinfunction "9_9") (pintype "passive"))
      (node (ref "J5") (pin "1") (pinfunction "1_1") (pintype "passive"))
      (node (ref "Q1") (pin "2") (pinfunction "S_2") (pintype "passive"))
      (node (ref "R14") (pin "1") (pinfunction "1_1") (pintype "passive"))
      (node (ref "R50") (pin "1") (pinfunction "1_1") (pintype "passive"))
      (node (ref "X5") (pin "15") (pinfunction "1_15") (pintype "passive"))
    )
    (net (code "152") (name "SI") (class "Default")
      (node (ref "IC1") (pin "29") (pinfunction "B1/28_29") (pintype "bidirectional"))
      (node (ref "X4") (pin "13") (pinfunction "1_13") (pintype "passive"))
    )
    (net (code "153") (name "SO") (class "Default")
      (node (ref "IC1") (pin "30") (pinfunction "B1/29_30") (pintype "bidirectional"))
      (node (ref "X4") (pin "12") (pinfunction "1_12") (pintype "passive"))
    )
    (net (code "154") (name "S_CLK") (class "Default")
      (node (ref "IC1") (pin "35") (pinfunction "B1/34_35") (pintype "bidirectional"))
      (node (ref "X4") (pin "11") (pinfunction "1_11") (pintype "passive"))
    )
    (net (code "155") (name "S_DIR") (class "Default")
      (node (ref "IC1") (pin "26") (pinfunction "B1/25_26") (pintype "bidirectional"))
      (node (ref "X4") (pin "14") (pinfunction "1_14") (pintype "passive"))
    )
    (net (code "156") (name "S_LATCH") (class "Default")
      (node (ref "IC1") (pin "27") (pinfunction "B1/26_27") (pintype "bidirectional"))
      (node (ref "X4") (pin "10") (pinfunction "1_10") (pintype "passive"))
    )
    (net (code "157") (name "S_RST") (class "Default")
      (node (ref "IC1") (pin "28") (pinfunction "B1/27_28") (pintype "bidirectional"))
      (node (ref "X5") (pin "12") (pinfunction "1_12") (pintype "passive"))
    )
    (net (code "158") (name "unconnected-(IC1-B1{slash}12-GCLK1-Pad14)") (class "Default")
      (node (ref "IC1") (pin "14") (pinfunction "B1/12-GCLK1_14") (pintype "bidirectional"))
    )
    (net (code "159") (name "unconnected-(IC1-B1{slash}13-Pad15)") (class "Default")
      (node (ref "IC1") (pin "15") (pinfunction "B1/13_15") (pintype "bidirectional"))
    )
    (net (code "160") (name "unconnected-(IC1-B1{slash}14-Pad16)") (class "Default")
      (node (ref "IC1") (pin "16") (pinfunction "B1/14_16") (pintype "bidirectional"))
    )
    (net (code "161") (name "unconnected-(IC1-B1{slash}16-Pad18)") (class "Default")
      (node (ref "IC1") (pin "18") (pinfunction "B1/16_18") (pintype "bidirectional"))
    )
    (net (code "162") (name "unconnected-(IC1-B1{slash}17-Pad19)") (class "Default")
      (node (ref "IC1") (pin "19") (pinfunction "B1/17_19") (pintype "bidirectional"))
    )
    (net (code "163") (name "unconnected-(IC1-B1{slash}18-Pad20)") (class "Default")
      (node (ref "IC1") (pin "20") (pinfunction "B1/18_20") (pintype "bidirectional"))
    )
    (net (code "164") (name "unconnected-(IC1-B1{slash}32-Pad33)") (class "Default")
      (node (ref "IC1") (pin "33") (pinfunction "B1/32_33") (pintype "bidirectional"))
    )
    (net (code "165") (name "unconnected-(IC1-B1{slash}33-Pad34)") (class "Default")
      (node (ref "IC1") (pin "34") (pinfunction "B1/33_34") (pintype "bidirectional"))
    )
    (net (code "166") (name "unconnected-(IC1-B1{slash}35-Pad36)") (class "Default")
      (node (ref "IC1") (pin "36") (pinfunction "B1/35_36") (pintype "bidirectional"))
    )
    (net (code "167") (name "unconnected-(IC1-B1{slash}36-Pad37)") (class "Default")
      (node (ref "IC1") (pin "37") (pinfunction "B1/36_37") (pintype "bidirectional"))
    )
    (net (code "168") (name "unconnected-(IC1-B1{slash}40-Pad41)") (class "Default")
      (node (ref "IC1") (pin "41") (pinfunction "B1/40_41") (pintype "bidirectional"))
    )
    (net (code "169") (name "unconnected-(IC1-B1{slash}41-Pad42)") (class "Default")
      (node (ref "IC1") (pin "42") (pinfunction "B1/41_42") (pintype "bidirectional"))
    )
    (net (code "170") (name "unconnected-(IC1-B1{slash}46-Pad47)") (class "Default")
      (node (ref "IC1") (pin "47") (pinfunction "B1/46_47") (pintype "bidirectional"))
    )
    (net (code "171") (name "unconnected-(IC1-B1{slash}47-Pad48)") (class "Default")
      (node (ref "IC1") (pin "48") (pinfunction "B1/47_48") (pintype "bidirectional"))
    )
    (net (code "172") (name "unconnected-(IC1-B1{slash}48-Pad49)") (class "Default")
      (node (ref "IC1") (pin "49") (pinfunction "B1/48_49") (pintype "bidirectional"))
    )
    (net (code "173") (name "unconnected-(IC1-B1{slash}50-Pad51)") (class "Default")
      (node (ref "IC1") (pin "51") (pinfunction "B1/50_51") (pintype "bidirectional"))
    )
    (net (code "174") (name "unconnected-(IC1-B2{slash}56-Pad57)") (class "Default")
      (node (ref "IC1") (pin "57") (pinfunction "B2/56_57") (pintype "bidirectional"))
    )
    (net (code "175") (name "unconnected-(IC1-B2{slash}61-GCLK2-Pad62)") (class "Default")
      (node (ref "IC1") (pin "62") (pinfunction "B2/61-GCLK2_62") (pintype "bidirectional"))
    )
    (net (code "176") (name "unconnected-(IC1-B2{slash}63-GCLK3-Pad64)") (class "Default")
      (node (ref "IC1") (pin "64") (pinfunction "B2/63-GCLK3_64") (pintype "bidirectional"))
    )
    (net (code "177") (name "unconnected-(IC1-B2{slash}66-Pad67)") (class "Default")
      (node (ref "IC1") (pin "67") (pinfunction "B2/66_67") (pintype "bidirectional"))
    )
    (net (code "178") (name "unconnected-(IC1-B2{slash}67-Pad68)") (class "Default")
      (node (ref "IC1") (pin "68") (pinfunction "B2/67_68") (pintype "bidirectional"))
    )
    (net (code "179") (name "unconnected-(IC1-B2{slash}68-Pad69)") (class "Default")
      (node (ref "IC1") (pin "69") (pinfunction "B2/68_69") (pintype "bidirectional"))
    )
    (net (code "180") (name "unconnected-(IC1-B2{slash}72-Pad73)") (class "Default")
      (node (ref "IC1") (pin "73") (pinfunction "B2/72_73") (pintype "bidirectional"))
    )
    (net (code "181") (name "unconnected-(IC1-B2{slash}75-Pad76)") (class "Default")
      (node (ref "IC1") (pin "76") (pinfunction "B2/75_76") (pintype "bidirectional"))
    )
    (net (code "182") (name "unconnected-(IC1-B2{slash}76-Pad77)") (class "Default")
      (node (ref "IC1") (pin "77") (pinfunction "B2/76_77") (pintype "bidirectional"))
    )
    (net (code "183") (name "unconnected-(IC1-B2{slash}80-Pad81)") (class "Default")
      (node (ref "IC1") (pin "81") (pinfunction "B2/80_81") (pintype "bidirectional"))
    )
    (net (code "184") (name "unconnected-(IC1-B2{slash}81-Pad82)") (class "Default")
      (node (ref "IC1") (pin "82") (pinfunction "B2/81_82") (pintype "bidirectional"))
    )
    (net (code "185") (name "unconnected-(IC1-B2{slash}82-Pad83)") (class "Default")
      (node (ref "IC1") (pin "83") (pinfunction "B2/82_83") (pintype "bidirectional"))
    )
    (net (code "186") (name "unconnected-(IC1-B2{slash}83-Pad84)") (class "Default")
      (node (ref "IC1") (pin "84") (pinfunction "B2/83_84") (pintype "bidirectional"))
    )
    (net (code "187") (name "unconnected-(IC1-B2{slash}85-Pad86)") (class "Default")
      (node (ref "IC1") (pin "86") (pinfunction "B2/85_86") (pintype "bidirectional"))
    )
    (net (code "188") (name "unconnected-(IC1-B2{slash}86-Pad87)") (class "Default")
      (node (ref "IC1") (pin "87") (pinfunction "B2/86_87") (pintype "bidirectional"))
    )
    (net (code "189") (name "unconnected-(IC1-B2{slash}87-Pad88)") (class "Default")
      (node (ref "IC1") (pin "88") (pinfunction "B2/87_88") (pintype "bidirectional"))
    )
    (net (code "190") (name "unconnected-(IC1-B2{slash}88-Pad89)") (class "Default")
      (node (ref "IC1") (pin "89") (pinfunction "B2/88_89") (pintype "bidirectional"))
    )
    (net (code "191") (name "unconnected-(IC1-B2{slash}89-Pad90)") (class "Default")
      (node (ref "IC1") (pin "90") (pinfunction "B2/89_90") (pintype "bidirectional"))
    )
    (net (code "192") (name "unconnected-(IC1-B2{slash}90-Pad91)") (class "Default")
      (node (ref "IC1") (pin "91") (pinfunction "B2/90_91") (pintype "bidirectional"))
    )
    (net (code "193") (name "unconnected-(IC1-B2{slash}91-Pad92)") (class "Default")
      (node (ref "IC1") (pin "92") (pinfunction "B2/91_92") (pintype "bidirectional"))
    )
    (net (code "194") (name "unconnected-(IC1-B2{slash}95-Pad96)") (class "Default")
      (node (ref "IC1") (pin "96") (pinfunction "B2/95_96") (pintype "bidirectional"))
    )
    (net (code "195") (name "unconnected-(IC1-B2{slash}96-Pad97)") (class "Default")
      (node (ref "IC1") (pin "97") (pinfunction "B2/96_97") (pintype "bidirectional"))
    )
    (net (code "196") (name "unconnected-(IC1-B2{slash}97-Pad98)") (class "Default")
      (node (ref "IC1") (pin "98") (pinfunction "B2/97_98") (pintype "bidirectional"))
    )
    (net (code "197") (name "unconnected-(IC1-B2{slash}98-Pad99)") (class "Default")
      (node (ref "IC1") (pin "99") (pinfunction "B2/98_99") (pintype "bidirectional"))
    )
    (net (code "198") (name "unconnected-(IC1-B2{slash}99-Pad100)") (class "Default")
      (node (ref "IC1") (pin "100") (pinfunction "B2/99_100") (pintype "bidirectional"))
    )
    (net (code "199") (name "unconnected-(J19-Pad1)") (class "Default")
      (node (ref "J19") (pin "1") (pinfunction "1_1") (pintype "passive"))
    )
    (net (code "200") (name "unconnected-(J19-Pad6)") (class "Default")
      (node (ref "J19") (pin "6") (pinfunction "6_6") (pintype "passive"))
    )
    (net (code "201") (name "unconnected-(JP1-Pad6)") (class "Default")
      (node (ref "JP1") (pin "6") (pinfunction "6_6") (pintype "passive"))
    )
    (net (code "202") (name "unconnected-(JP1-Pad7)") (class "Default")
      (node (ref "JP1") (pin "7") (pinfunction "7_7") (pintype "passive"))
    )
    (net (code "203") (name "unconnected-(JP1-Pad8)") (class "Default")
      (node (ref "JP1") (pin "8") (pinfunction "8_8") (pintype "passive"))
    )
    (net (code "204") (name "unconnected-(JP5-Pad4)") (class "Default")
      (node (ref "JP5") (pin "4") (pinfunction "4_4") (pintype "passive"))
    )
    (net (code "205") (name "unconnected-(JP5-Pad7)") (class "Default")
      (node (ref "JP5") (pin "7") (pinfunction "7_7") (pintype "passive"))
    )
    (net (code "206") (name "unconnected-(JP5-Pad9)") (class "Default")
      (node (ref "JP5") (pin "9") (pinfunction "9_9") (pintype "passive"))
    )
    (net (code "207") (name "unconnected-(U2-T1IN-Pad11)") (class "Default")
      (node (ref "U2") (pin "11") (pinfunction "T1IN_11") (pintype "input"))
    )
    (net (code "208") (name "unconnected-(U2-T1OUT-Pad14)") (class "Default")
      (node (ref "U2") (pin "14") (pinfunction "T1OUT_14") (pintype "output"))
    )
    (net (code "209") (name "unconnected-(U3-NC-Pad4)") (class "Default")
      (node (ref "U3") (pin "4") (pinfunction "NC_4") (pintype "no_connect"))
    )
    (net (code "210") (name "unconnected-(U4-OSC-Pad7)") (class "Default")
      (node (ref "U4") (pin "7") (pinfunction "OSC_7") (pintype "input"))
    )
    (net (code "211") (name "unconnected-(X2-5VREF-Pad5)") (class "Default")
      (node (ref "X2") (pin "5") (pinfunction "5VREF_5") (pintype "bidirectional"))
    )
    (net (code "212") (name "unconnected-(X4-Pad1)") (class "Default")
      (node (ref "X4") (pin "1") (pinfunction "1_1") (pintype "passive"))
    )
    (net (code "213") (name "unconnected-(X4I-1-Pad17)") (class "Default")
      (node (ref "X4") (pin "17") (pinfunction "1_17") (pintype "passive"))
    )
    (net (code "214") (name "unconnected-(X4J-1-Pad18)") (class "Default")
      (node (ref "X4") (pin "18") (pinfunction "1_18") (pintype "passive"))
    )
    (net (code "215") (name "unconnected-(X4L-1-Pad2)") (class "Default")
      (node (ref "X4") (pin "2") (pinfunction "1_2") (pintype "passive"))
    )
    (net (code "216") (name "unconnected-(X4Q-1-Pad4)") (class "Default")
      (node (ref "X4") (pin "4") (pinfunction "1_4") (pintype "passive"))
    )
    (net (code "217") (name "unconnected-(X4R-1-Pad5)") (class "Default")
      (node (ref "X4") (pin "5") (pinfunction "1_5") (pintype "passive"))
    )
    (net (code "218") (name "unconnected-(X5P-1-Pad3)") (class "Default")
      (node (ref "X5") (pin "3") (pinfunction "1_3") (pintype "passive"))
    )
    (net (code "219") (name "unconnected-(X5Q-1-Pad4)") (class "Default")
      (node (ref "X5") (pin "4") (pinfunction "1_4") (pintype "passive"))
    )
    (net (code "220") (name "unconnected-(X5S-1-Pad6)") (class "Default")
      (node (ref "X5") (pin "6") (pinfunction "1_6") (pintype "passive"))
    )
    (net (code "221") (name "unconnected-(X5T-1-Pad7)") (class "Default")
      (node (ref "X5") (pin "7") (pinfunction "1_7") (pintype "passive"))
    )
  )
)
